# smart_auto_charger_2020-04-23_15-03-07.net
KiCad netlist of a schematic drawn in EasyEDA
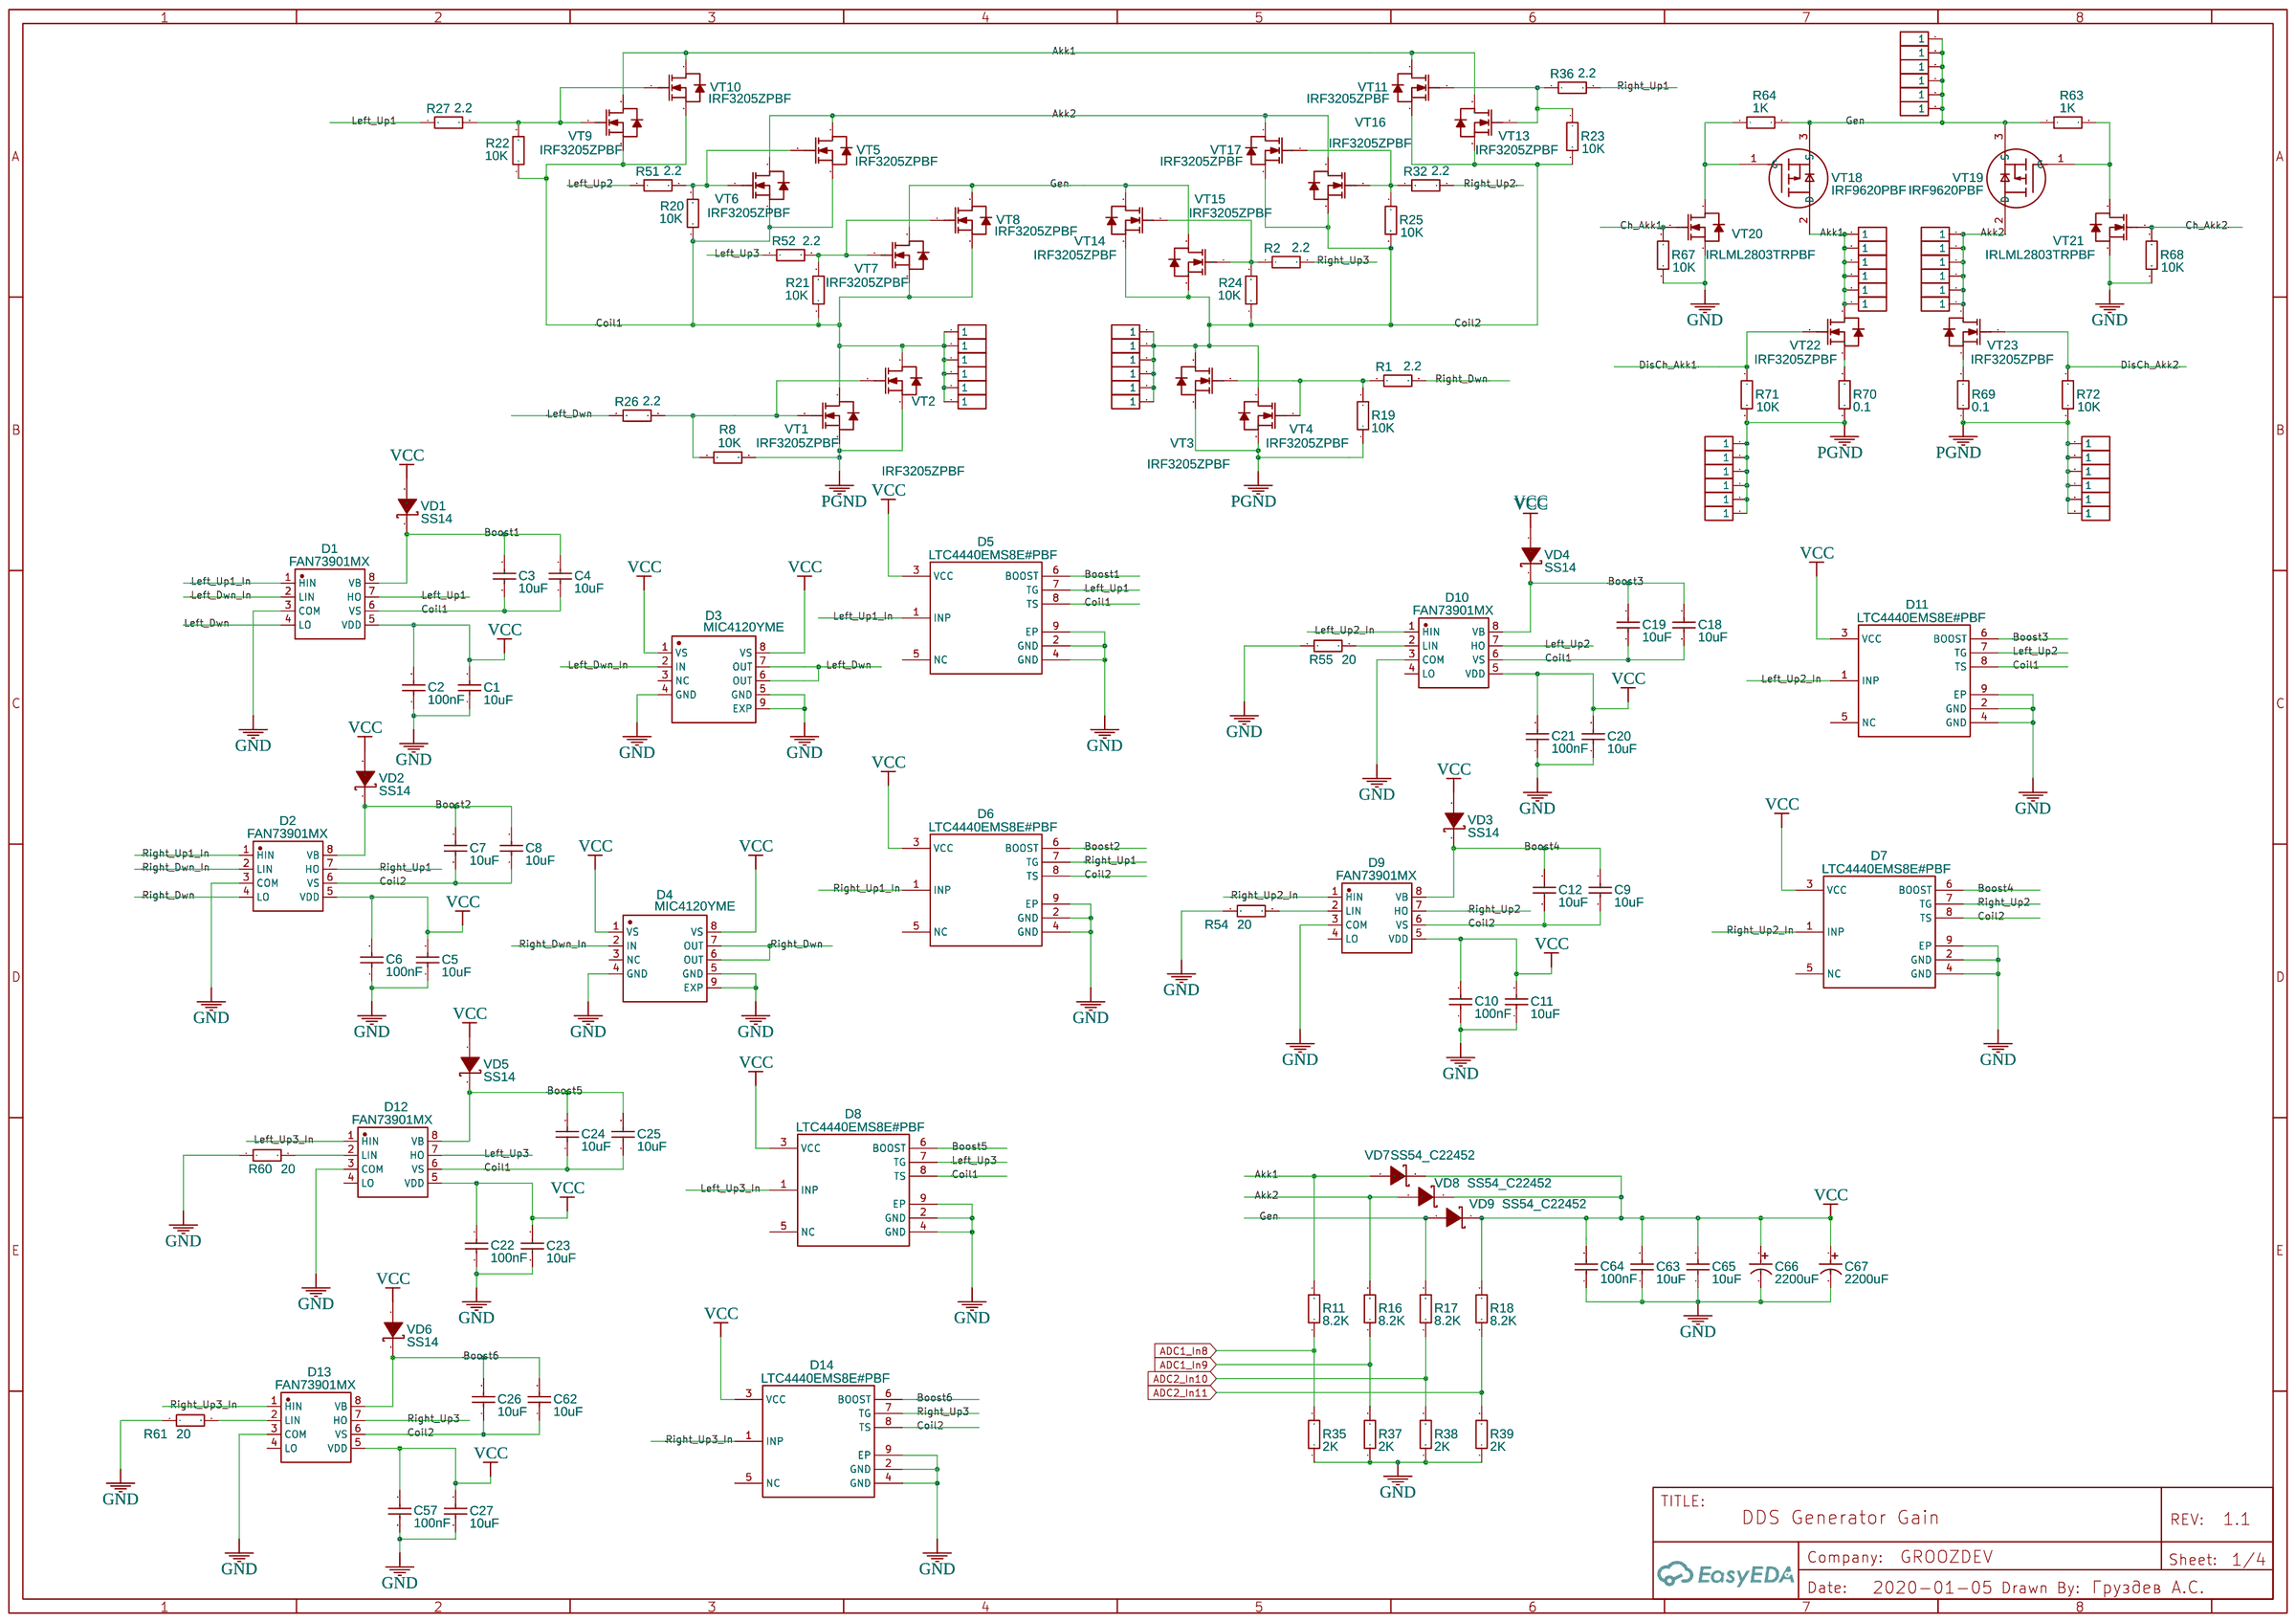
[diagram p0: First stage]
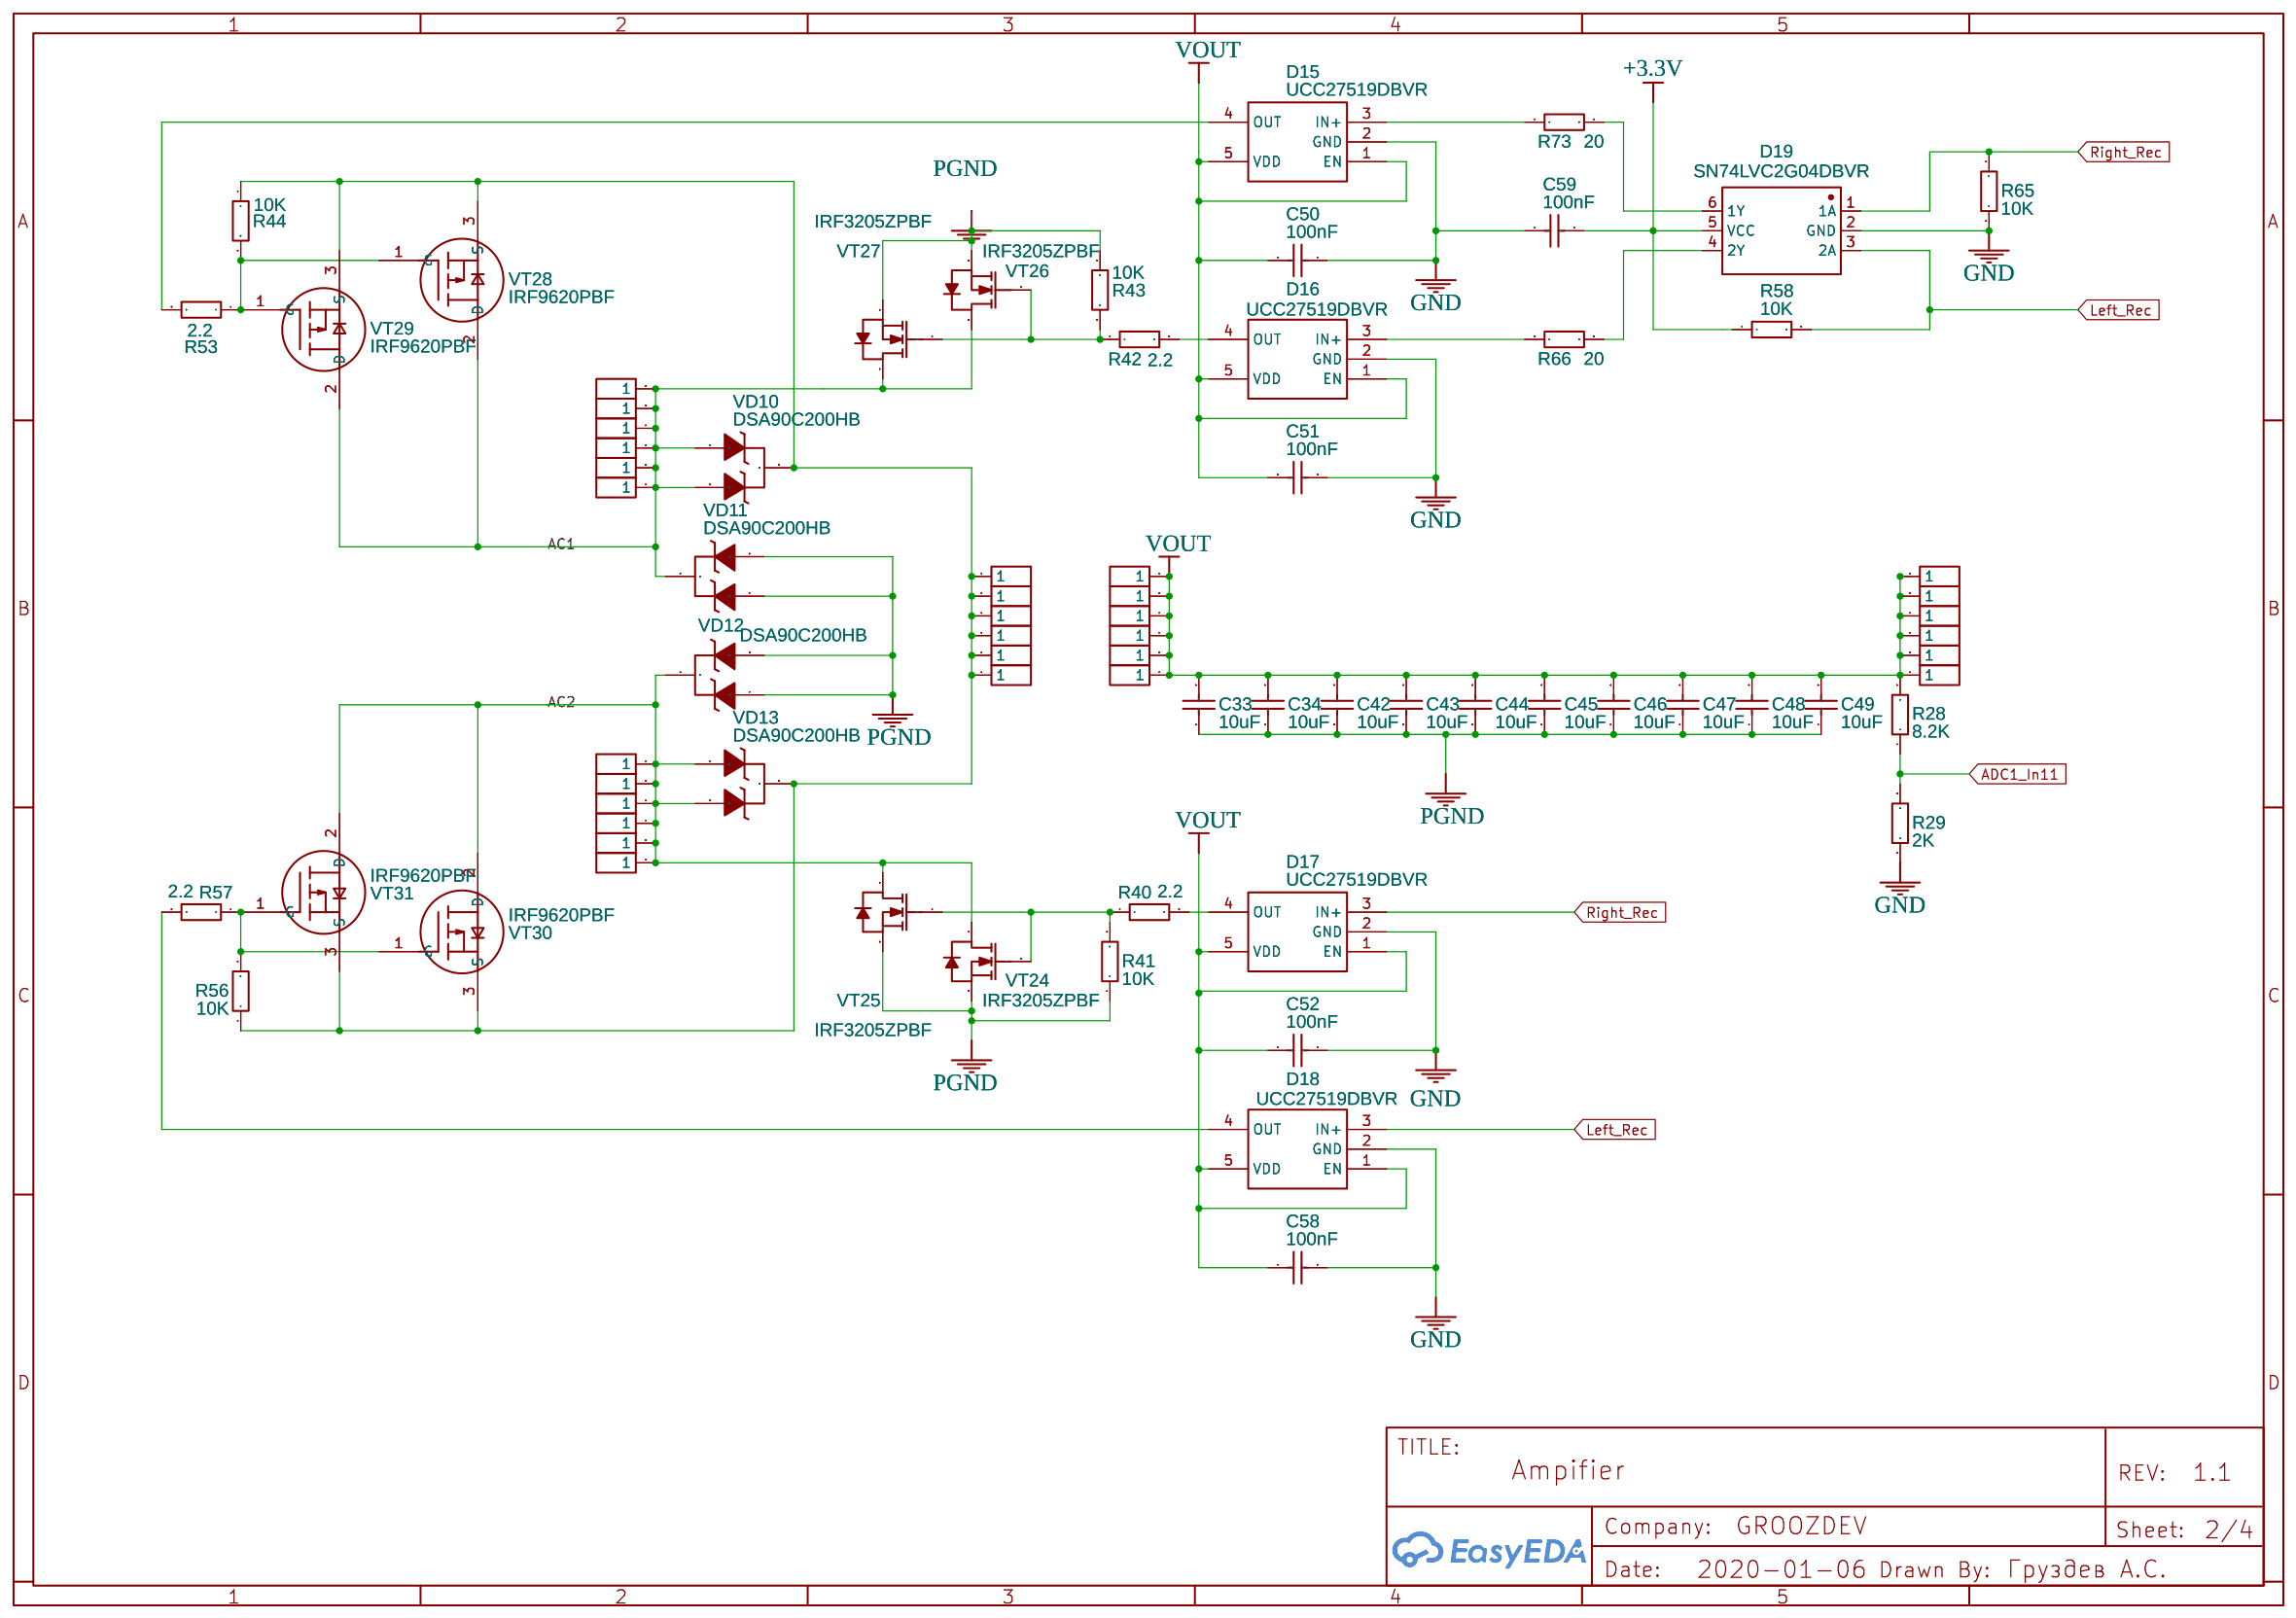
[diagram p1: Second stage]
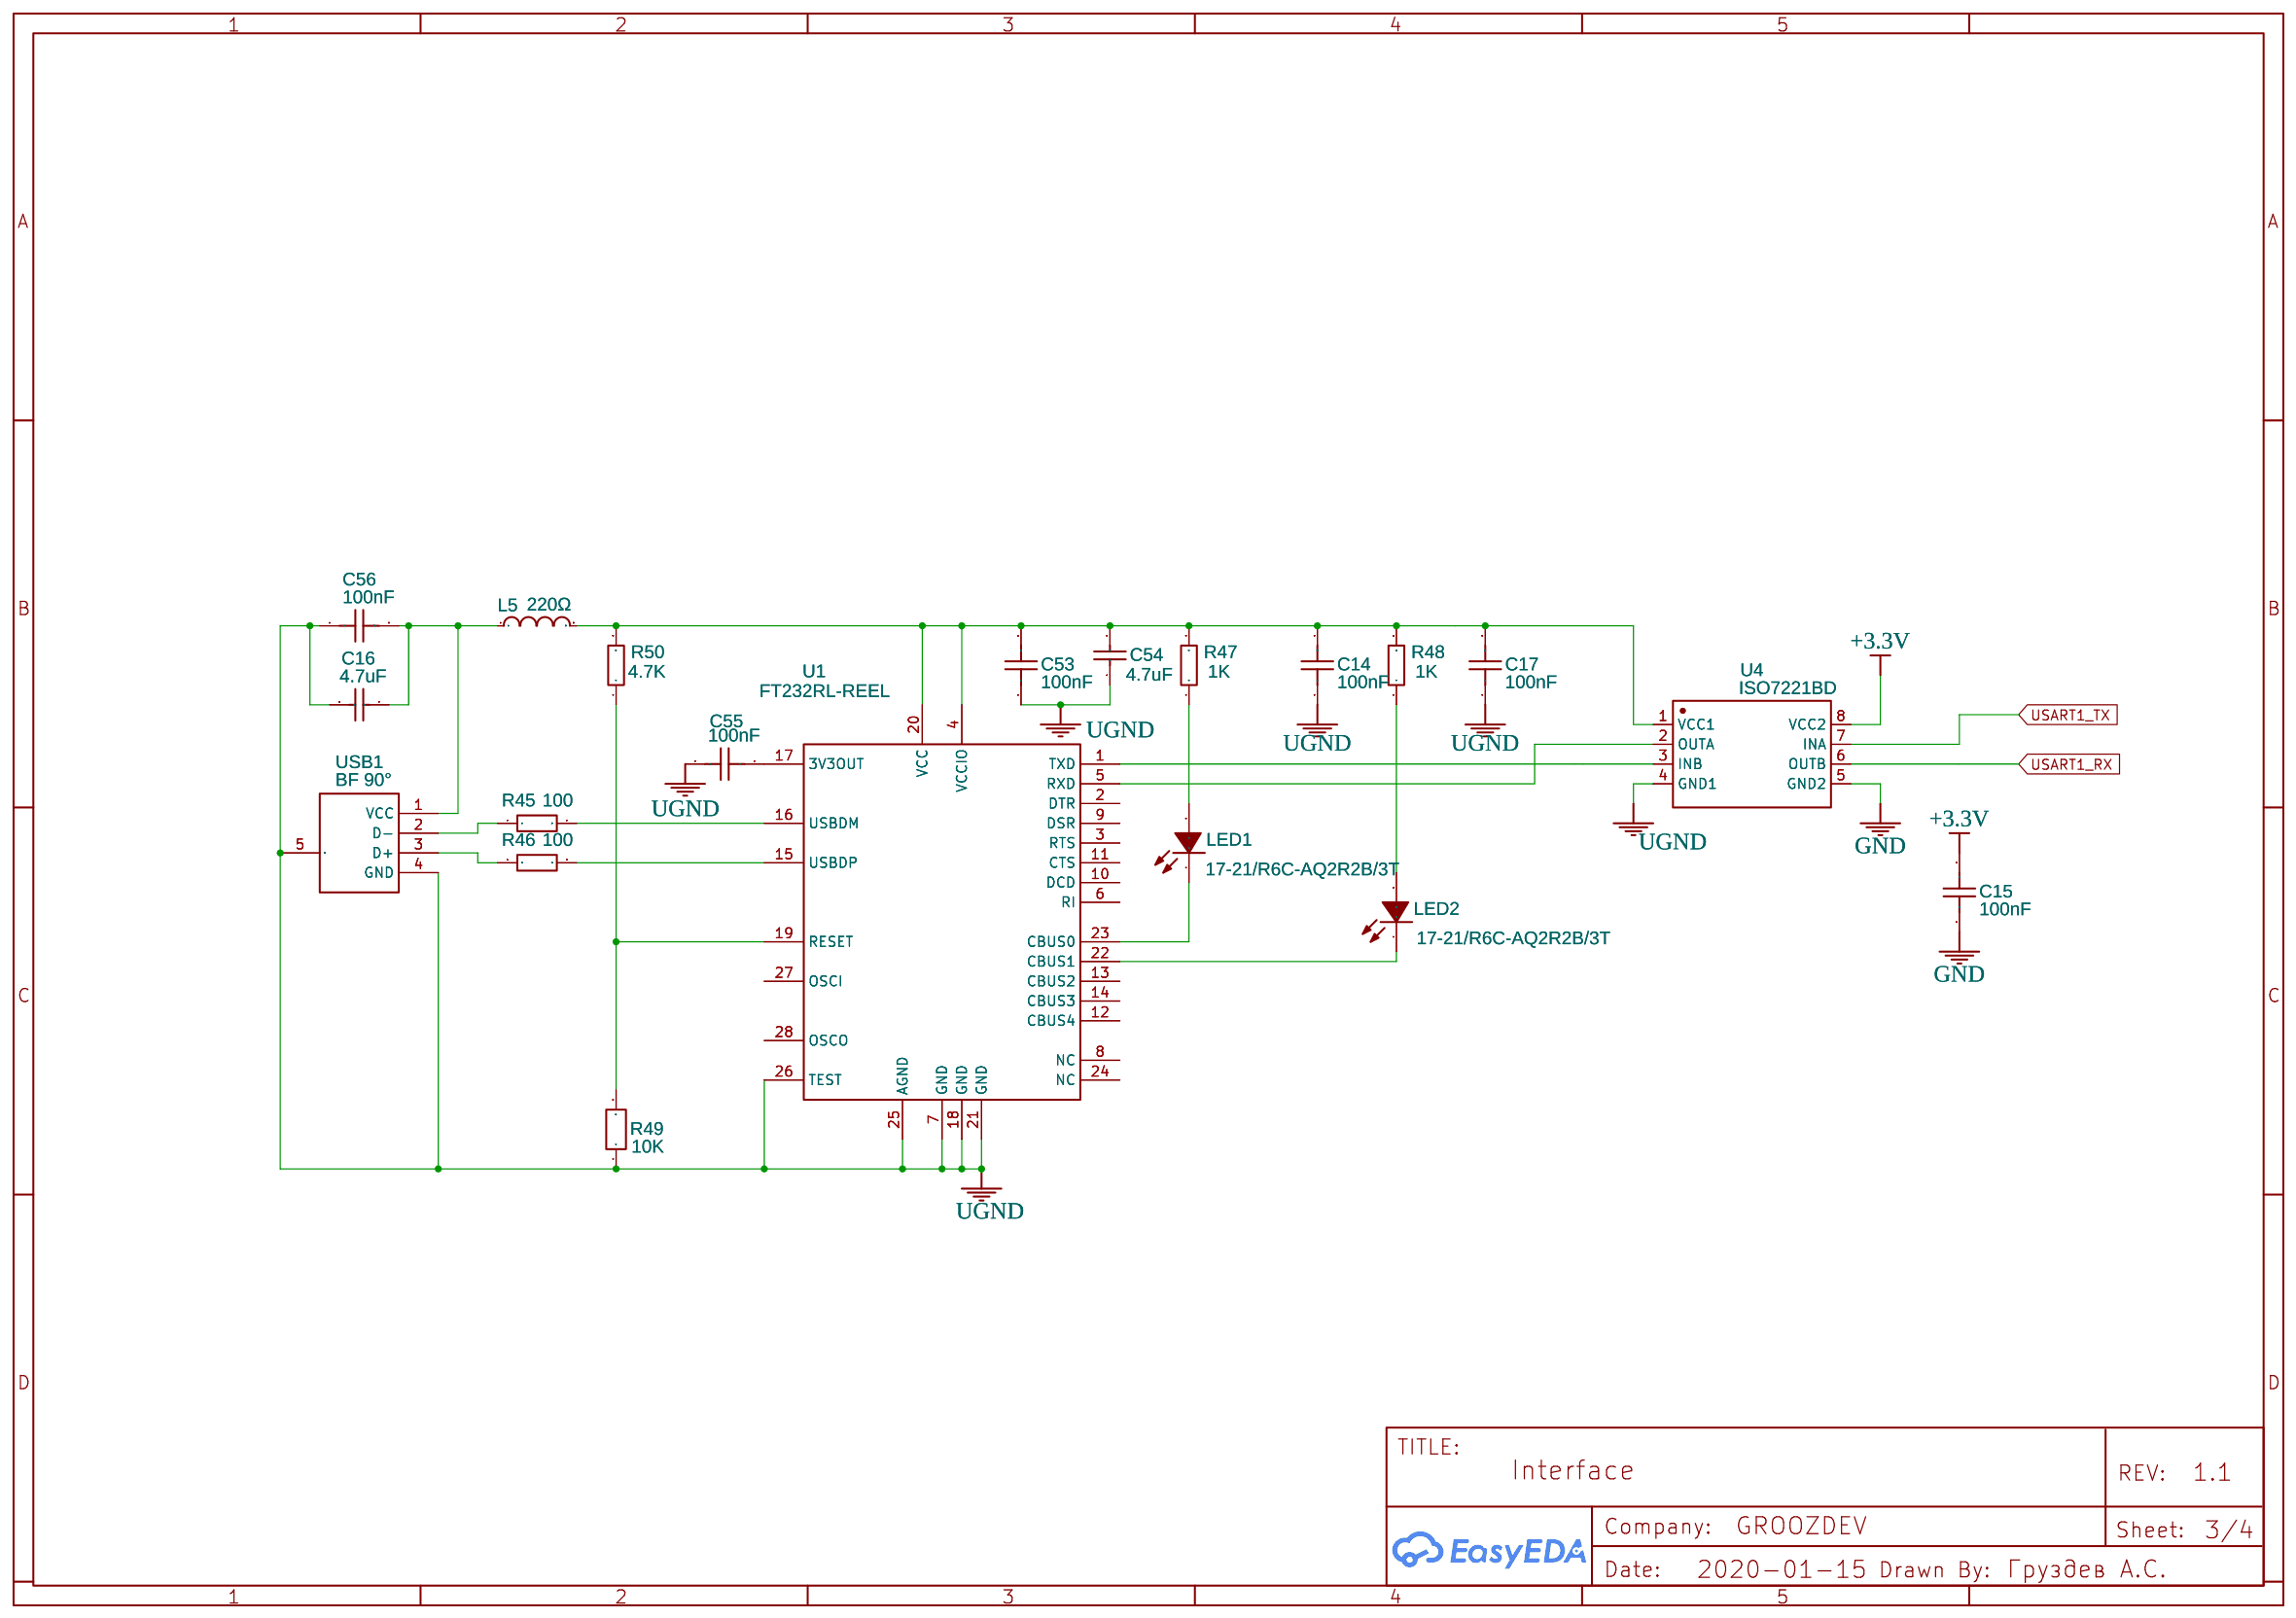
[diagram p2: USBtoVirtualCOM]
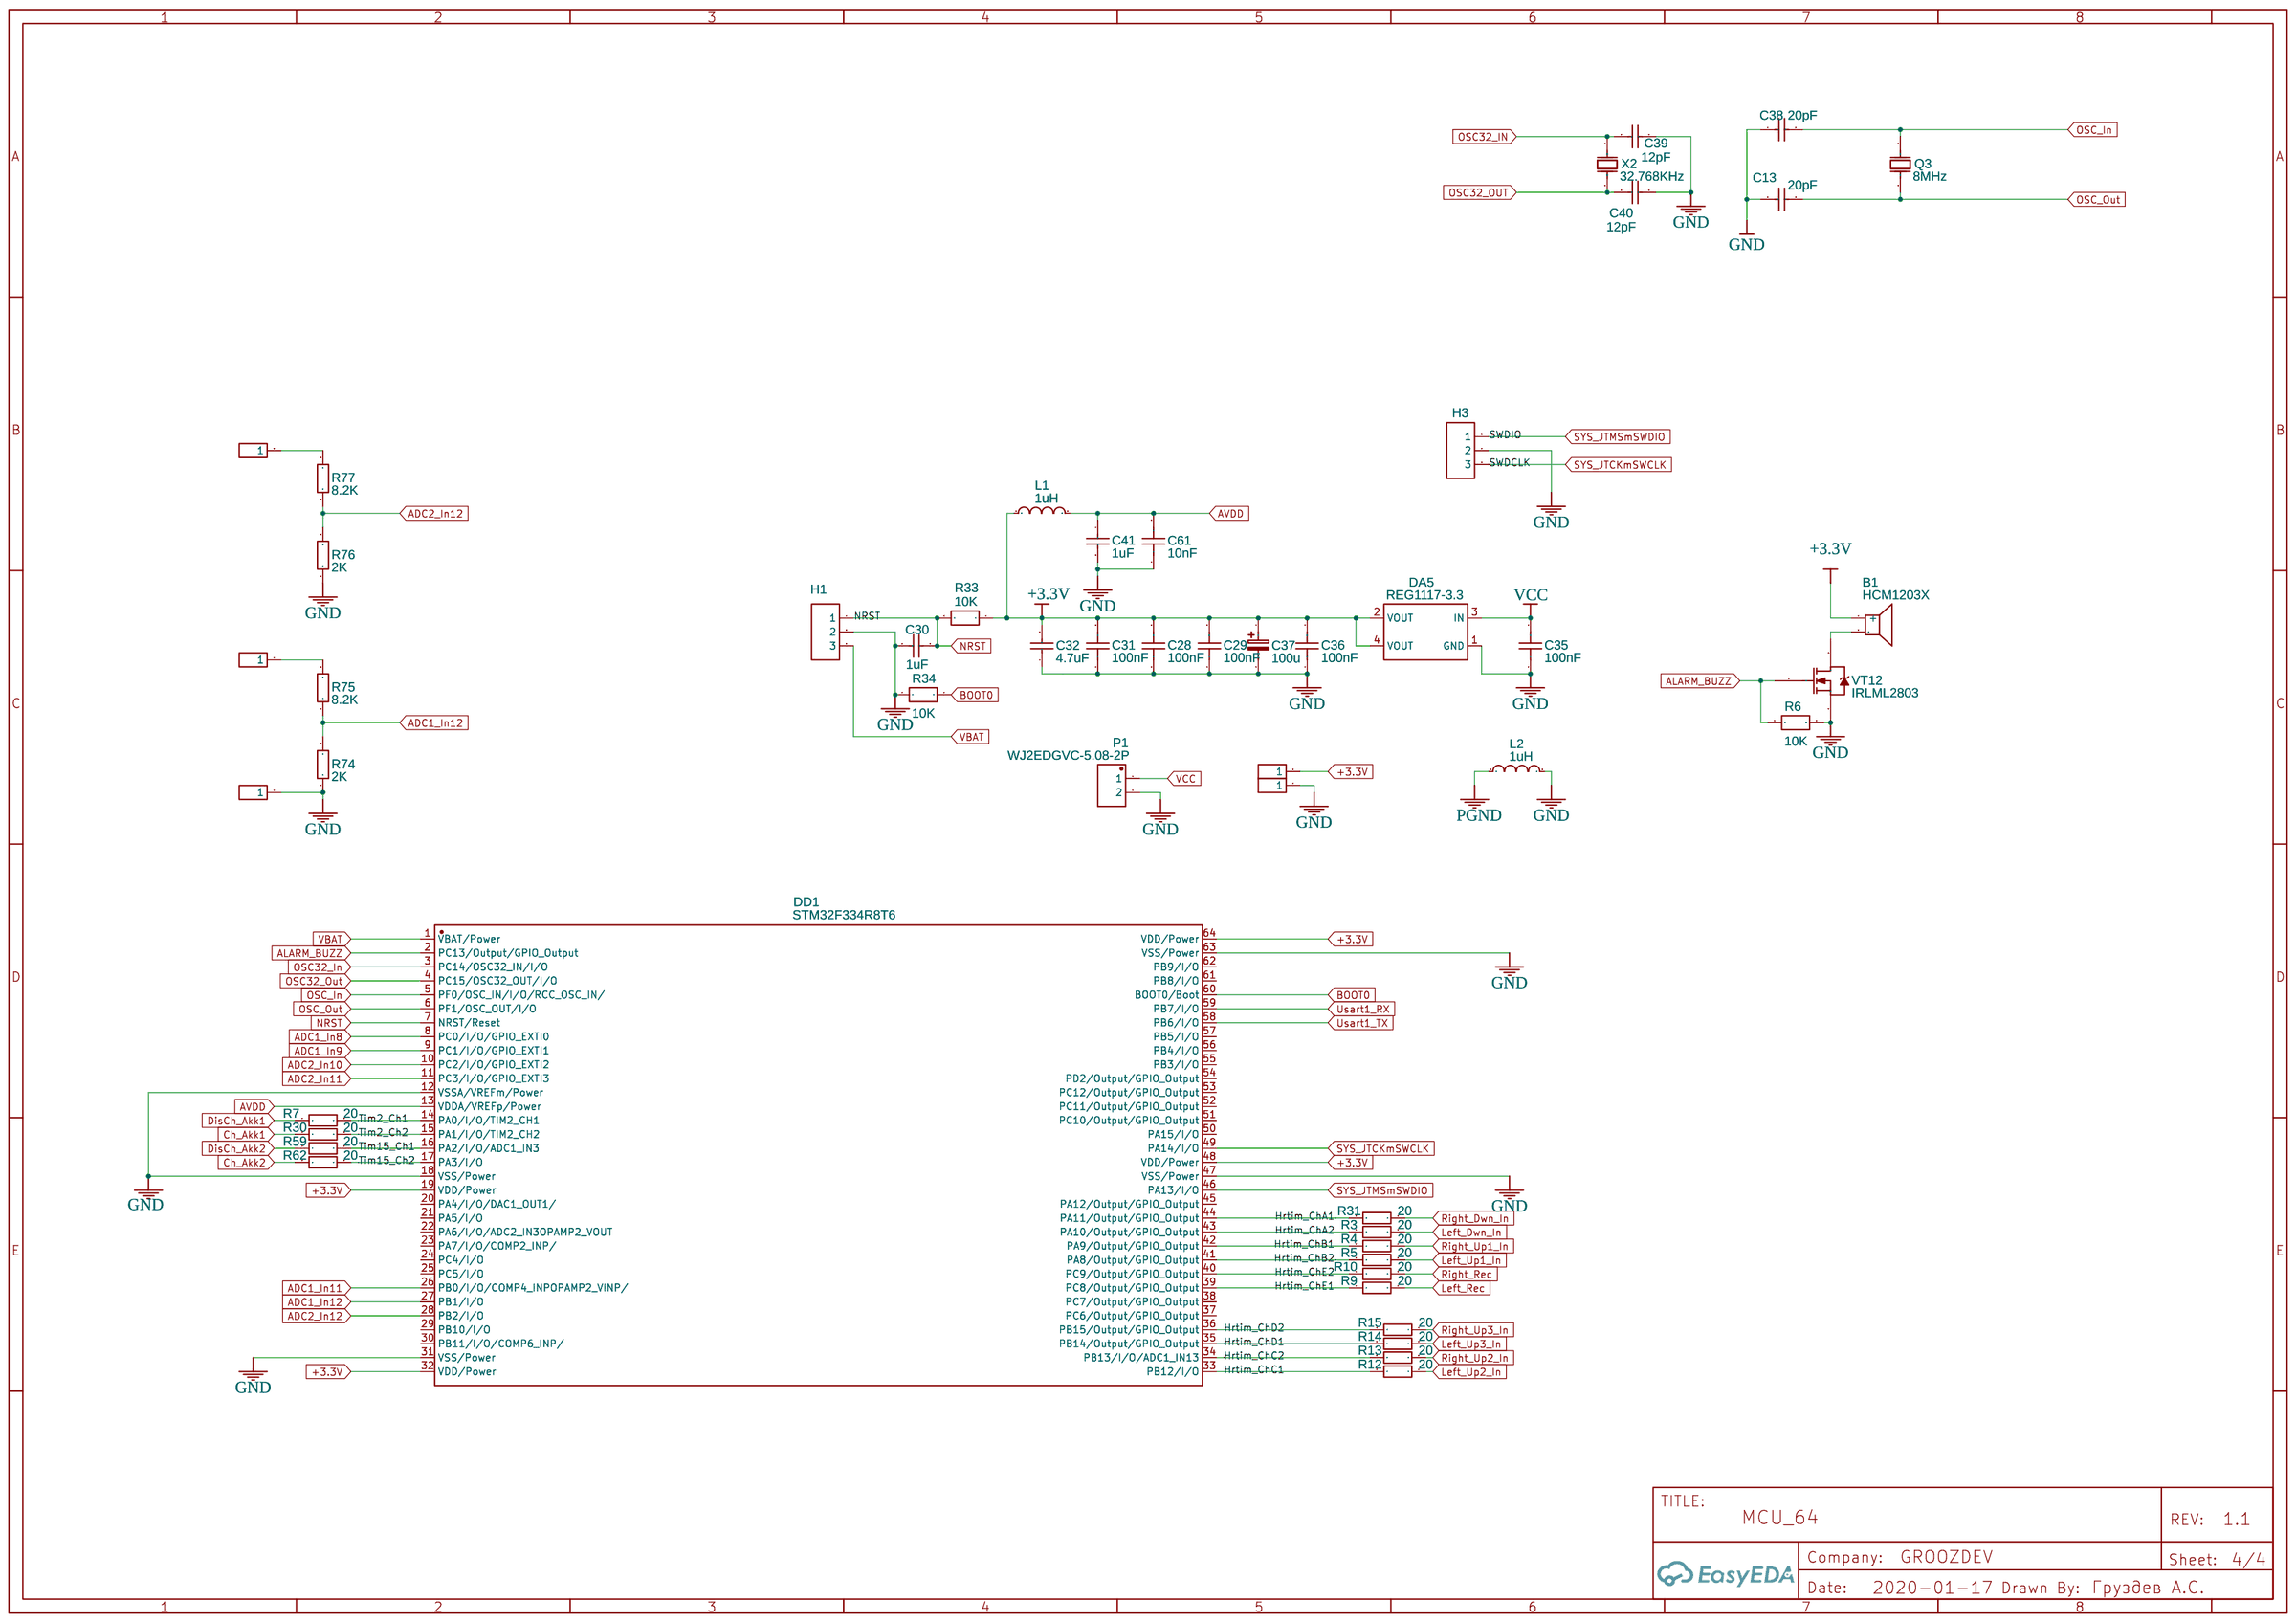
[diagram p3: MCU_64]

(export (version "E")
  (design (tool "Eeschema 10.0.6"))
  (components
    (comp (ref "C1")
      (value "10uF")
      (fields
        (field (name "BOM_Manufacturer Part") "CL31A106KBHNNNE")
        (field (name "BOM_Supplier Part") "C13585")
      )
      (libsource (lib "") (part "CL31A106KBHNNNE"))
    )
    (comp (ref "C2")
      (value "100nF")
      (fields
        (field (name "BOM_Manufacturer Part") "CL31B104KCFNNNE")
        (field (name "BOM_Supplier Part") "C1945")
      )
      (libsource (lib "") (part "CL31B104KCFNNNE"))
    )
    (comp (ref "C3")
      (value "10uF")
      (fields
        (field (name "BOM_Manufacturer Part") "CL31A106KBHNNNE")
        (field (name "BOM_Supplier Part") "C13585")
      )
      (libsource (lib "") (part "CL31A106KBHNNNE"))
    )
    (comp (ref "C4")
      (value "10uF")
      (fields
        (field (name "BOM_Manufacturer Part") "CL31A106KBHNNNE")
        (field (name "BOM_Supplier Part") "C13585")
      )
      (libsource (lib "") (part "CL31A106KBHNNNE"))
    )
    (comp (ref "C5")
      (value "10uF")
      (fields
        (field (name "BOM_Manufacturer Part") "CL31A106KBHNNNE")
        (field (name "BOM_Supplier Part") "C13585")
      )
      (libsource (lib "") (part "CL31A106KBHNNNE"))
    )
    (comp (ref "C6")
      (value "100nF")
      (fields
        (field (name "BOM_Manufacturer Part") "CL31B104KCFNNNE")
        (field (name "BOM_Supplier Part") "C1945")
      )
      (libsource (lib "") (part "CL31B104KCFNNNE"))
    )
    (comp (ref "C7")
      (value "10uF")
      (fields
        (field (name "BOM_Manufacturer Part") "CL31A106KBHNNNE")
        (field (name "BOM_Supplier Part") "C13585")
      )
      (libsource (lib "") (part "CL31A106KBHNNNE"))
    )
    (comp (ref "C8")
      (value "10uF")
      (fields
        (field (name "BOM_Manufacturer Part") "CL31A106KBHNNNE")
        (field (name "BOM_Supplier Part") "C13585")
      )
      (libsource (lib "") (part "CL31A106KBHNNNE"))
    )
    (comp (ref "C9")
      (value "10uF")
      (fields
        (field (name "BOM_Manufacturer Part") "CL31A106KBHNNNE")
        (field (name "BOM_Supplier Part") "C13585")
      )
      (libsource (lib "") (part "CL31A106KBHNNNE"))
    )
    (comp (ref "C10")
      (value "100nF")
      (fields
        (field (name "BOM_Manufacturer Part") "CL31B104KCFNNNE")
        (field (name "BOM_Supplier Part") "C1945")
      )
      (libsource (lib "") (part "CL31B104KCFNNNE"))
    )
    (comp (ref "C11")
      (value "10uF")
      (fields
        (field (name "BOM_Manufacturer Part") "CL31A106KBHNNNE")
        (field (name "BOM_Supplier Part") "C13585")
      )
      (libsource (lib "") (part "CL31A106KBHNNNE"))
    )
    (comp (ref "C12")
      (value "10uF")
      (fields
        (field (name "BOM_Manufacturer Part") "CL31A106KBHNNNE")
        (field (name "BOM_Supplier Part") "C13585")
      )
      (libsource (lib "") (part "CL31A106KBHNNNE"))
    )
    (comp (ref "C18")
      (value "10uF")
      (fields
        (field (name "BOM_Manufacturer Part") "CL31A106KBHNNNE")
        (field (name "BOM_Supplier Part") "C13585")
      )
      (libsource (lib "") (part "CL31A106KBHNNNE"))
    )
    (comp (ref "C19")
      (value "10uF")
      (fields
        (field (name "BOM_Manufacturer Part") "CL31A106KBHNNNE")
        (field (name "BOM_Supplier Part") "C13585")
      )
      (libsource (lib "") (part "CL31A106KBHNNNE"))
    )
    (comp (ref "C20")
      (value "10uF")
      (fields
        (field (name "BOM_Manufacturer Part") "CL31A106KBHNNNE")
        (field (name "BOM_Supplier Part") "C13585")
      )
      (libsource (lib "") (part "CL31A106KBHNNNE"))
    )
    (comp (ref "C21")
      (value "100nF")
      (fields
        (field (name "BOM_Manufacturer Part") "CL31B104KCFNNNE")
        (field (name "BOM_Supplier Part") "C1945")
      )
      (libsource (lib "") (part "CL31B104KCFNNNE"))
    )
    (comp (ref "C22")
      (value "100nF")
      (fields
        (field (name "BOM_Manufacturer Part") "CL31B104KCFNNNE")
        (field (name "BOM_Supplier Part") "C1945")
      )
      (libsource (lib "") (part "CL31B104KCFNNNE"))
    )
    (comp (ref "C23")
      (value "10uF")
      (fields
        (field (name "BOM_Manufacturer Part") "CL31A106KBHNNNE")
        (field (name "BOM_Supplier Part") "C13585")
      )
      (libsource (lib "") (part "CL31A106KBHNNNE"))
    )
    (comp (ref "C24")
      (value "10uF")
      (fields
        (field (name "BOM_Manufacturer Part") "CL31A106KBHNNNE")
        (field (name "BOM_Supplier Part") "C13585")
      )
      (libsource (lib "") (part "CL31A106KBHNNNE"))
    )
    (comp (ref "C25")
      (value "10uF")
      (fields
        (field (name "BOM_Manufacturer Part") "CL31A106KBHNNNE")
        (field (name "BOM_Supplier Part") "C13585")
      )
      (libsource (lib "") (part "CL31A106KBHNNNE"))
    )
    (comp (ref "C26")
      (value "10uF")
      (fields
        (field (name "BOM_Manufacturer Part") "CL31A106KBHNNNE")
        (field (name "BOM_Supplier Part") "C13585")
      )
      (libsource (lib "") (part "CL31A106KBHNNNE"))
    )
    (comp (ref "C27")
      (value "10uF")
      (fields
        (field (name "BOM_Manufacturer Part") "CL31A106KBHNNNE")
        (field (name "BOM_Supplier Part") "C13585")
      )
      (libsource (lib "") (part "CL31A106KBHNNNE"))
    )
    (comp (ref "C57")
      (value "100nF")
      (fields
        (field (name "BOM_Manufacturer Part") "CL31B104KCFNNNE")
        (field (name "BOM_Supplier Part") "C1945")
      )
      (libsource (lib "") (part "CL31B104KCFNNNE"))
    )
    (comp (ref "C62")
      (value "10uF")
      (fields
        (field (name "BOM_Manufacturer Part") "CL31A106KBHNNNE")
        (field (name "BOM_Supplier Part") "C13585")
      )
      (libsource (lib "") (part "CL31A106KBHNNNE"))
    )
    (comp (ref "C63")
      (value "10uF")
      (fields
        (field (name "BOM_Manufacturer Part") "CL31A106KBHNNNE")
        (field (name "BOM_Supplier Part") "C13585")
      )
      (libsource (lib "") (part "CL31A106KBHNNNE"))
    )
    (comp (ref "C64")
      (value "100nF")
      (fields
        (field (name "BOM_Manufacturer Part") "CL31B104KCFNNNE")
        (field (name "BOM_Supplier Part") "C1945")
      )
      (libsource (lib "") (part "CL31B104KCFNNNE"))
    )
    (comp (ref "C65")
      (value "10uF")
      (fields
        (field (name "BOM_Manufacturer Part") "CL31A106KBHNNNE")
        (field (name "BOM_Supplier Part") "C13585")
      )
      (libsource (lib "") (part "CL31A106KBHNNNE"))
    )
    (comp (ref "C66")
      (value "2200uF")
      (fields
        (field (name "BOM_Manufacturer Part") "2200uF 35V 16X25")
        (field (name "BOM_Supplier Part") "C2763")
      )
      (libsource (lib "") (part "2200uF 35V 16X25"))
    )
    (comp (ref "C67")
      (value "2200uF")
      (fields
        (field (name "BOM_Manufacturer Part") "2200uF 35V 16X25")
        (field (name "BOM_Supplier Part") "C2763")
      )
      (libsource (lib "") (part "2200uF 35V 16X25"))
    )
    (comp (ref "D1")
      (value "FAN73901MX")
      (fields (field (name "BOM_Supplier Part") "C380794"))
      (libsource (lib "") (part "FAN73901MX"))
    )
    (comp (ref "D2")
      (value "FAN73901MX")
      (fields (field (name "BOM_Supplier Part") "C380794"))
      (libsource (lib "") (part "FAN73901MX"))
    )
    (comp (ref "D3")
      (value "MIC4120YME")
      (fields (field (name "BOM_Supplier Part") "C145580"))
      (libsource (lib "") (part "MIC4120YME"))
    )
    (comp (ref "D4")
      (value "MIC4120YME")
      (fields (field (name "BOM_Supplier Part") "C145580"))
      (libsource (lib "") (part "MIC4120YME"))
    )
    (comp (ref "D5")
      (value "LTC4440EMS8E#PBF")
      (fields (field (name "BOM_Supplier Part") "C107973"))
      (libsource (lib "") (part "LTC4440EMS8E#PBF"))
    )
    (comp (ref "D6")
      (value "LTC4440EMS8E#PBF")
      (fields (field (name "BOM_Supplier Part") "C107973"))
      (libsource (lib "") (part "LTC4440EMS8E#PBF"))
    )
    (comp (ref "D7")
      (value "LTC4440EMS8E#PBF")
      (fields (field (name "BOM_Supplier Part") "C107973"))
      (libsource (lib "") (part "LTC4440EMS8E#PBF"))
    )
    (comp (ref "D8")
      (value "LTC4440EMS8E#PBF")
      (fields (field (name "BOM_Supplier Part") "C107973"))
      (libsource (lib "") (part "LTC4440EMS8E#PBF"))
    )
    (comp (ref "D9")
      (value "FAN73901MX")
      (fields (field (name "BOM_Supplier Part") "C380794"))
      (libsource (lib "") (part "FAN73901MX"))
    )
    (comp (ref "D10")
      (value "FAN73901MX")
      (fields (field (name "BOM_Supplier Part") "C380794"))
      (libsource (lib "") (part "FAN73901MX"))
    )
    (comp (ref "D11")
      (value "LTC4440EMS8E#PBF")
      (fields (field (name "BOM_Supplier Part") "C107973"))
      (libsource (lib "") (part "LTC4440EMS8E#PBF"))
    )
    (comp (ref "D12")
      (value "FAN73901MX")
      (fields (field (name "BOM_Supplier Part") "C380794"))
      (libsource (lib "") (part "FAN73901MX"))
    )
    (comp (ref "D13")
      (value "FAN73901MX")
      (fields (field (name "BOM_Supplier Part") "C380794"))
      (libsource (lib "") (part "FAN73901MX"))
    )
    (comp (ref "D14")
      (value "LTC4440EMS8E#PBF")
      (fields (field (name "BOM_Supplier Part") "C107973"))
      (libsource (lib "") (part "LTC4440EMS8E#PBF"))
    )
    (comp (ref "P4")
      (value "Header-Male-2.54_1x1")
      (fields (field (name "BOM_Supplier Part") "C81276"))
      (libsource (lib "") (part "Header-Male-2.54_1x1_1"))
    )
    (comp (ref "P5")
      (value "Header-Male-2.54_1x1")
      (fields (field (name "BOM_Supplier Part") "C81276"))
      (libsource (lib "") (part "Header-Male-2.54_1x1_1"))
    )
    (comp (ref "P6")
      (value "Header-Male-2.54_1x1")
      (fields (field (name "BOM_Supplier Part") "C81276"))
      (libsource (lib "") (part "Header-Male-2.54_1x1_1"))
    )
    (comp (ref "P7")
      (value "Header-Male-2.54_1x1")
      (fields (field (name "BOM_Supplier Part") "C81276"))
      (libsource (lib "") (part "Header-Male-2.54_1x1"))
    )
    (comp (ref "P8")
      (value "Header-Male-2.54_1x1")
      (fields (field (name "BOM_Supplier Part") "C81276"))
      (libsource (lib "") (part "Header-Male-2.54_1x1"))
    )
    (comp (ref "P9")
      (value "Header-Male-2.54_1x1")
      (fields (field (name "BOM_Supplier Part") "C81276"))
      (libsource (lib "") (part "Header-Male-2.54_1x1"))
    )
    (comp (ref "P10")
      (value "Header-Male-2.54_1x1")
      (fields (field (name "BOM_Supplier Part") "C81276"))
      (libsource (lib "") (part "Header-Male-2.54_1x1_1"))
    )
    (comp (ref "P11")
      (value "Header-Male-2.54_1x1")
      (fields (field (name "BOM_Supplier Part") "C81276"))
      (libsource (lib "") (part "Header-Male-2.54_1x1_1"))
    )
    (comp (ref "P12")
      (value "Header-Male-2.54_1x1")
      (fields (field (name "BOM_Supplier Part") "C81276"))
      (libsource (lib "") (part "Header-Male-2.54_1x1_1"))
    )
    (comp (ref "P13")
      (value "Header-Male-2.54_1x1")
      (fields (field (name "BOM_Supplier Part") "C81276"))
      (libsource (lib "") (part "Header-Male-2.54_1x1"))
    )
    (comp (ref "P14")
      (value "Header-Male-2.54_1x1")
      (fields (field (name "BOM_Supplier Part") "C81276"))
      (libsource (lib "") (part "Header-Male-2.54_1x1"))
    )
    (comp (ref "P15")
      (value "Header-Male-2.54_1x1")
      (fields (field (name "BOM_Supplier Part") "C81276"))
      (libsource (lib "") (part "Header-Male-2.54_1x1"))
    )
    (comp (ref "P16")
      (value "Header-Male-2.54_1x1")
      (fields (field (name "BOM_Supplier Part") "C81276"))
      (libsource (lib "") (part "Header-Male-2.54_1x1"))
    )
    (comp (ref "P17")
      (value "Header-Male-2.54_1x1")
      (fields (field (name "BOM_Supplier Part") "C81276"))
      (libsource (lib "") (part "Header-Male-2.54_1x1"))
    )
    (comp (ref "P32")
      (value "Header-Male-2.54_1x1")
      (fields (field (name "BOM_Supplier Part") "C81276"))
      (libsource (lib "") (part "Header-Male-2.54_1x1"))
    )
    (comp (ref "P33")
      (value "Header-Male-2.54_1x1")
      (fields (field (name "BOM_Supplier Part") "C81276"))
      (libsource (lib "") (part "Header-Male-2.54_1x1_1"))
    )
    (comp (ref "P34")
      (value "Header-Male-2.54_1x1")
      (fields (field (name "BOM_Supplier Part") "C81276"))
      (libsource (lib "") (part "Header-Male-2.54_1x1_1"))
    )
    (comp (ref "P35")
      (value "Header-Male-2.54_1x1")
      (fields (field (name "BOM_Supplier Part") "C81276"))
      (libsource (lib "") (part "Header-Male-2.54_1x1_1"))
    )
    (comp (ref "P36")
      (value "Header-Male-2.54_1x1")
      (fields (field (name "BOM_Supplier Part") "C81276"))
      (libsource (lib "") (part "Header-Male-2.54_1x1_1"))
    )
    (comp (ref "P37")
      (value "Header-Male-2.54_1x1")
      (fields (field (name "BOM_Supplier Part") "C81276"))
      (libsource (lib "") (part "Header-Male-2.54_1x1"))
    )
    (comp (ref "P38")
      (value "Header-Male-2.54_1x1")
      (fields (field (name "BOM_Supplier Part") "C81276"))
      (libsource (lib "") (part "Header-Male-2.54_1x1"))
    )
    (comp (ref "P39")
      (value "Header-Male-2.54_1x1")
      (fields (field (name "BOM_Supplier Part") "C81276"))
      (libsource (lib "") (part "Header-Male-2.54_1x1"))
    )
    (comp (ref "P40")
      (value "Header-Male-2.54_1x1")
      (fields (field (name "BOM_Supplier Part") "C81276"))
      (libsource (lib "") (part "Header-Male-2.54_1x1_1"))
    )
    (comp (ref "P41")
      (value "Header-Male-2.54_1x1")
      (fields (field (name "BOM_Supplier Part") "C81276"))
      (libsource (lib "") (part "Header-Male-2.54_1x1_1"))
    )
    (comp (ref "P42")
      (value "Header-Male-2.54_1x1")
      (fields (field (name "BOM_Supplier Part") "C81276"))
      (libsource (lib "") (part "Header-Male-2.54_1x1"))
    )
    (comp (ref "P43")
      (value "Header-Male-2.54_1x1")
      (fields (field (name "BOM_Supplier Part") "C81276"))
      (libsource (lib "") (part "Header-Male-2.54_1x1"))
    )
    (comp (ref "P44")
      (value "Header-Male-2.54_1x1")
      (fields (field (name "BOM_Supplier Part") "C81276"))
      (libsource (lib "") (part "Header-Male-2.54_1x1"))
    )
    (comp (ref "P45")
      (value "Header-Male-2.54_1x1")
      (fields (field (name "BOM_Supplier Part") "C81276"))
      (libsource (lib "") (part "Header-Male-2.54_1x1"))
    )
    (comp (ref "P46")
      (value "Header-Male-2.54_1x1")
      (fields (field (name "BOM_Supplier Part") "C81276"))
      (libsource (lib "") (part "Header-Male-2.54_1x1"))
    )
    (comp (ref "P47")
      (value "Header-Male-2.54_1x1")
      (fields (field (name "BOM_Supplier Part") "C81276"))
      (libsource (lib "") (part "Header-Male-2.54_1x1"))
    )
    (comp (ref "P48")
      (value "Header-Male-2.54_1x1")
      (fields (field (name "BOM_Supplier Part") "C81276"))
      (libsource (lib "") (part "Header-Male-2.54_1x1"))
    )
    (comp (ref "P49")
      (value "Header-Male-2.54_1x1")
      (fields (field (name "BOM_Supplier Part") "C81276"))
      (libsource (lib "") (part "Header-Male-2.54_1x1"))
    )
    (comp (ref "P50")
      (value "Header-Male-2.54_1x1")
      (fields (field (name "BOM_Supplier Part") "C81276"))
      (libsource (lib "") (part "Header-Male-2.54_1x1"))
    )
    (comp (ref "P51")
      (value "Header-Male-2.54_1x1")
      (fields (field (name "BOM_Supplier Part") "C81276"))
      (libsource (lib "") (part "Header-Male-2.54_1x1"))
    )
    (comp (ref "P52")
      (value "Header-Male-2.54_1x1")
      (fields (field (name "BOM_Supplier Part") "C81276"))
      (libsource (lib "") (part "Header-Male-2.54_1x1"))
    )
    (comp (ref "P53")
      (value "Header-Male-2.54_1x1")
      (fields (field (name "BOM_Supplier Part") "C81276"))
      (libsource (lib "") (part "Header-Male-2.54_1x1"))
    )
    (comp (ref "P54")
      (value "Header-Male-2.54_1x1")
      (fields (field (name "BOM_Supplier Part") "C81276"))
      (libsource (lib "") (part "Header-Male-2.54_1x1_1"))
    )
    (comp (ref "P55")
      (value "Header-Male-2.54_1x1")
      (fields (field (name "BOM_Supplier Part") "C81276"))
      (libsource (lib "") (part "Header-Male-2.54_1x1_1"))
    )
    (comp (ref "P56")
      (value "Header-Male-2.54_1x1")
      (fields (field (name "BOM_Supplier Part") "C81276"))
      (libsource (lib "") (part "Header-Male-2.54_1x1_1"))
    )
    (comp (ref "P57")
      (value "Header-Male-2.54_1x1")
      (fields (field (name "BOM_Supplier Part") "C81276"))
      (libsource (lib "") (part "Header-Male-2.54_1x1_1"))
    )
    (comp (ref "P58")
      (value "Header-Male-2.54_1x1")
      (fields (field (name "BOM_Supplier Part") "C81276"))
      (libsource (lib "") (part "Header-Male-2.54_1x1_1"))
    )
    (comp (ref "P59")
      (value "Header-Male-2.54_1x1")
      (fields (field (name "BOM_Supplier Part") "C81276"))
      (libsource (lib "") (part "Header-Male-2.54_1x1_1"))
    )
    (comp (ref "R1")
      (value "2.2")
      (fields
        (field (name "BOM_Manufacturer Part") "0603WAF220KT5E")
        (field (name "BOM_Supplier Part") "C22939")
      )
      (libsource (lib "") (part "0603WAF220KT5E"))
    )
    (comp (ref "R2")
      (value "2.2")
      (fields
        (field (name "BOM_Manufacturer Part") "0603WAF220KT5E")
        (field (name "BOM_Supplier Part") "C22939")
      )
      (libsource (lib "") (part "0603WAF220KT5E"))
    )
    (comp (ref "R8")
      (value "10K")
      (fields
        (field (name "BOM_Manufacturer Part") "0805W8F1002T5E")
        (field (name "BOM_Supplier Part") "C17414")
      )
      (libsource (lib "") (part "0805W8F1002T5E_2"))
    )
    (comp (ref "R11")
      (value "8.2K")
      (fields
        (field (name "BOM_Manufacturer Part") "0805W8F8201T5E")
        (field (name "BOM_Supplier Part") "C17828")
      )
      (libsource (lib "") (part "0805W8F8201T5E"))
    )
    (comp (ref "R16")
      (value "8.2K")
      (fields
        (field (name "BOM_Manufacturer Part") "0805W8F8201T5E")
        (field (name "BOM_Supplier Part") "C17828")
      )
      (libsource (lib "") (part "0805W8F8201T5E"))
    )
    (comp (ref "R17")
      (value "8.2K")
      (fields
        (field (name "BOM_Manufacturer Part") "0805W8F8201T5E")
        (field (name "BOM_Supplier Part") "C17828")
      )
      (libsource (lib "") (part "0805W8F8201T5E"))
    )
    (comp (ref "R18")
      (value "8.2K")
      (fields
        (field (name "BOM_Manufacturer Part") "0805W8F8201T5E")
        (field (name "BOM_Supplier Part") "C17828")
      )
      (libsource (lib "") (part "0805W8F8201T5E"))
    )
    (comp (ref "R19")
      (value "10K")
      (fields
        (field (name "BOM_Manufacturer Part") "0805W8F1002T5E")
        (field (name "BOM_Supplier Part") "C17414")
      )
      (libsource (lib "") (part "0805W8F1002T5E"))
    )
    (comp (ref "R20")
      (value "10K")
      (fields
        (field (name "BOM_Manufacturer Part") "0805W8F1002T5E")
        (field (name "BOM_Supplier Part") "C17414")
      )
      (libsource (lib "") (part "0805W8F1002T5E"))
    )
    (comp (ref "R21")
      (value "10K")
      (fields
        (field (name "BOM_Manufacturer Part") "0805W8F1002T5E")
        (field (name "BOM_Supplier Part") "C17414")
      )
      (libsource (lib "") (part "0805W8F1002T5E"))
    )
    (comp (ref "R22")
      (value "10K")
      (fields
        (field (name "BOM_Manufacturer Part") "0805W8F1002T5E")
        (field (name "BOM_Supplier Part") "C17414")
      )
      (libsource (lib "") (part "0805W8F1002T5E"))
    )
    (comp (ref "R23")
      (value "10K")
      (fields
        (field (name "BOM_Manufacturer Part") "0805W8F1002T5E")
        (field (name "BOM_Supplier Part") "C17414")
      )
      (libsource (lib "") (part "0805W8F1002T5E_1"))
    )
    (comp (ref "R24")
      (value "10K")
      (fields
        (field (name "BOM_Manufacturer Part") "0805W8F1002T5E")
        (field (name "BOM_Supplier Part") "C17414")
      )
      (libsource (lib "") (part "0805W8F1002T5E"))
    )
    (comp (ref "R25")
      (value "10K")
      (fields
        (field (name "BOM_Manufacturer Part") "0805W8F1002T5E")
        (field (name "BOM_Supplier Part") "C17414")
      )
      (libsource (lib "") (part "0805W8F1002T5E_1"))
    )
    (comp (ref "R26")
      (value "2.2")
      (fields
        (field (name "BOM_Manufacturer Part") "0603WAF220KT5E")
        (field (name "BOM_Supplier Part") "C22939")
      )
      (libsource (lib "") (part "0603WAF220KT5E"))
    )
    (comp (ref "R27")
      (value "2.2")
      (fields
        (field (name "BOM_Manufacturer Part") "0603WAF220KT5E")
        (field (name "BOM_Supplier Part") "C22939")
      )
      (libsource (lib "") (part "0603WAF220KT5E"))
    )
    (comp (ref "R32")
      (value "2.2")
      (fields
        (field (name "BOM_Manufacturer Part") "0603WAF220KT5E")
        (field (name "BOM_Supplier Part") "C22939")
      )
      (libsource (lib "") (part "0603WAF220KT5E"))
    )
    (comp (ref "R35")
      (value "2K")
      (fields
        (field (name "BOM_Manufacturer Part") "0805W8F2001T5E")
        (field (name "BOM_Supplier Part") "C17604")
      )
      (libsource (lib "") (part "0805W8F2001T5E"))
    )
    (comp (ref "R36")
      (value "2.2")
      (fields
        (field (name "BOM_Manufacturer Part") "0603WAF220KT5E")
        (field (name "BOM_Supplier Part") "C22939")
      )
      (libsource (lib "") (part "0603WAF220KT5E"))
    )
    (comp (ref "R37")
      (value "2K")
      (fields
        (field (name "BOM_Manufacturer Part") "0805W8F2001T5E")
        (field (name "BOM_Supplier Part") "C17604")
      )
      (libsource (lib "") (part "0805W8F2001T5E"))
    )
    (comp (ref "R38")
      (value "2K")
      (fields
        (field (name "BOM_Manufacturer Part") "0805W8F2001T5E")
        (field (name "BOM_Supplier Part") "C17604")
      )
      (libsource (lib "") (part "0805W8F2001T5E"))
    )
    (comp (ref "R39")
      (value "2K")
      (fields
        (field (name "BOM_Manufacturer Part") "0805W8F2001T5E")
        (field (name "BOM_Supplier Part") "C17604")
      )
      (libsource (lib "") (part "0805W8F2001T5E"))
    )
    (comp (ref "R51")
      (value "2.2")
      (fields
        (field (name "BOM_Manufacturer Part") "0603WAF220KT5E")
        (field (name "BOM_Supplier Part") "C22939")
      )
      (libsource (lib "") (part "0603WAF220KT5E"))
    )
    (comp (ref "R52")
      (value "2.2")
      (fields
        (field (name "BOM_Manufacturer Part") "0603WAF220KT5E")
        (field (name "BOM_Supplier Part") "C22939")
      )
      (libsource (lib "") (part "0603WAF220KT5E"))
    )
    (comp (ref "R54")
      (value "20")
      (fields
        (field (name "BOM_Manufacturer Part") "0603WAF200JT5E")
        (field (name "BOM_Supplier Part") "C22950")
      )
      (libsource (lib "") (part "0603WAF200JT5E"))
    )
    (comp (ref "R55")
      (value "20")
      (fields
        (field (name "BOM_Manufacturer Part") "0603WAF200JT5E")
        (field (name "BOM_Supplier Part") "C22950")
      )
      (libsource (lib "") (part "0603WAF200JT5E"))
    )
    (comp (ref "R60")
      (value "20")
      (fields
        (field (name "BOM_Manufacturer Part") "0603WAF200JT5E")
        (field (name "BOM_Supplier Part") "C22950")
      )
      (libsource (lib "") (part "0603WAF200JT5E"))
    )
    (comp (ref "R61")
      (value "20")
      (fields
        (field (name "BOM_Manufacturer Part") "0603WAF200JT5E")
        (field (name "BOM_Supplier Part") "C22950")
      )
      (libsource (lib "") (part "0603WAF200JT5E"))
    )
    (comp (ref "R63")
      (value "1K")
      (fields
        (field (name "BOM_Manufacturer Part") "1206W4F1001T5E")
        (field (name "BOM_Supplier Part") "C4410")
      )
      (libsource (lib "") (part "1206W4F1001T5E"))
    )
    (comp (ref "R64")
      (value "1K")
      (fields
        (field (name "BOM_Manufacturer Part") "1206W4F1001T5E")
        (field (name "BOM_Supplier Part") "C4410")
      )
      (libsource (lib "") (part "1206W4F1001T5E"))
    )
    (comp (ref "R67")
      (value "10K")
      (fields
        (field (name "BOM_Manufacturer Part") "0805W8F1002T5E")
        (field (name "BOM_Supplier Part") "C17414")
      )
      (libsource (lib "") (part "0805W8F1002T5E_1"))
    )
    (comp (ref "R68")
      (value "10K")
      (fields
        (field (name "BOM_Manufacturer Part") "0805W8F1002T5E")
        (field (name "BOM_Supplier Part") "C17414")
      )
      (libsource (lib "") (part "0805W8F1002T5E_1"))
    )
    (comp (ref "R69")
      (value "0.1")
      (fields
        (field (name "BOM_Manufacturer Part") "MRF6432(2512)LR100FTS")
        (field (name "BOM_Supplier Part") "C76254")
      )
      (libsource (lib "") (part "MRF6432(2512)LR100FTS"))
    )
    (comp (ref "R70")
      (value "0.1")
      (fields
        (field (name "BOM_Manufacturer Part") "MRF6432(2512)LR100FTS")
        (field (name "BOM_Supplier Part") "C76254")
      )
      (libsource (lib "") (part "MRF6432(2512)LR100FTS"))
    )
    (comp (ref "R71")
      (value "10K")
      (fields
        (field (name "BOM_Manufacturer Part") "0805W8F1002T5E")
        (field (name "BOM_Supplier Part") "C17414")
      )
      (libsource (lib "") (part "0805W8F1002T5E_1"))
    )
    (comp (ref "R72")
      (value "10K")
      (fields
        (field (name "BOM_Manufacturer Part") "0805W8F1002T5E")
        (field (name "BOM_Supplier Part") "C17414")
      )
      (libsource (lib "") (part "0805W8F1002T5E_1"))
    )
    (comp (ref "VD1")
      (value "SS14")
      (fields (field (name "BOM_Supplier Part") "C2480"))
      (libsource (lib "") (part "SS14"))
    )
    (comp (ref "VD2")
      (value "SS14")
      (fields (field (name "BOM_Supplier Part") "C2480"))
      (libsource (lib "") (part "SS14"))
    )
    (comp (ref "VD3")
      (value "SS14")
      (fields (field (name "BOM_Supplier Part") "C2480"))
      (libsource (lib "") (part "SS14"))
    )
    (comp (ref "VD4")
      (value "SS14")
      (fields (field (name "BOM_Supplier Part") "C2480"))
      (libsource (lib "") (part "SS14"))
    )
    (comp (ref "VD5")
      (value "SS14")
      (fields (field (name "BOM_Supplier Part") "C2480"))
      (libsource (lib "") (part "SS14"))
    )
    (comp (ref "VD6")
      (value "SS14")
      (fields (field (name "BOM_Supplier Part") "C2480"))
      (libsource (lib "") (part "SS14"))
    )
    (comp (ref "VD7")
      (value "SS54_C22452")
      (fields (field (name "BOM_Manufacturer Part") "SS54") (field (name "BOM_Supplier Part") "C22452"))
      (libsource (lib "") (part "SS54_C22452"))
    )
    (comp (ref "VD8")
      (value "SS54_C22452")
      (fields (field (name "BOM_Manufacturer Part") "SS54") (field (name "BOM_Supplier Part") "C22452"))
      (libsource (lib "") (part "SS54_C22452"))
    )
    (comp (ref "VD9")
      (value "SS54_C22452")
      (fields (field (name "BOM_Manufacturer Part") "SS54") (field (name "BOM_Supplier Part") "C22452"))
      (libsource (lib "") (part "SS54_C22452"))
    )
    (comp (ref "VT1")
      (value "IRF3205ZPBF")
      (fields (field (name "BOM_Supplier Part") "C2612"))
      (libsource (lib "") (part "IRF3205ZPBF"))
    )
    (comp (ref "VT2")
      (value "IRF3205ZPBF")
      (fields (field (name "BOM_Supplier Part") "C2612"))
      (libsource (lib "") (part "IRF3205ZPBF"))
    )
    (comp (ref "VT3")
      (value "IRF3205ZPBF")
      (fields (field (name "BOM_Supplier Part") "C2612"))
      (libsource (lib "") (part "IRF3205ZPBF_1"))
    )
    (comp (ref "VT4")
      (value "IRF3205ZPBF")
      (fields (field (name "BOM_Supplier Part") "C2612"))
      (libsource (lib "") (part "IRF3205ZPBF_1"))
    )
    (comp (ref "VT5")
      (value "IRF3205ZPBF")
      (fields (field (name "BOM_Supplier Part") "C2612"))
      (libsource (lib "") (part "IRF3205ZPBF"))
    )
    (comp (ref "VT6")
      (value "IRF3205ZPBF")
      (fields (field (name "BOM_Supplier Part") "C2612"))
      (libsource (lib "") (part "IRF3205ZPBF"))
    )
    (comp (ref "VT7")
      (value "IRF3205ZPBF")
      (fields (field (name "BOM_Supplier Part") "C2612"))
      (libsource (lib "") (part "IRF3205ZPBF"))
    )
    (comp (ref "VT8")
      (value "IRF3205ZPBF")
      (fields (field (name "BOM_Supplier Part") "C2612"))
      (libsource (lib "") (part "IRF3205ZPBF"))
    )
    (comp (ref "VT9")
      (value "IRF3205ZPBF")
      (fields (field (name "BOM_Supplier Part") "C2612"))
      (libsource (lib "") (part "IRF3205ZPBF"))
    )
    (comp (ref "VT10")
      (value "IRF3205ZPBF")
      (fields (field (name "BOM_Supplier Part") "C2612"))
      (libsource (lib "") (part "IRF3205ZPBF"))
    )
    (comp (ref "VT11")
      (value "IRF3205ZPBF")
      (fields (field (name "BOM_Supplier Part") "C2612"))
      (libsource (lib "") (part "IRF3205ZPBF_1"))
    )
    (comp (ref "VT13")
      (value "IRF3205ZPBF")
      (fields (field (name "BOM_Supplier Part") "C2612"))
      (libsource (lib "") (part "IRF3205ZPBF_1"))
    )
    (comp (ref "VT14")
      (value "IRF3205ZPBF")
      (fields (field (name "BOM_Supplier Part") "C2612"))
      (libsource (lib "") (part "IRF3205ZPBF_1"))
    )
    (comp (ref "VT15")
      (value "IRF3205ZPBF")
      (fields (field (name "BOM_Supplier Part") "C2612"))
      (libsource (lib "") (part "IRF3205ZPBF_1"))
    )
    (comp (ref "VT16")
      (value "IRF3205ZPBF")
      (fields (field (name "BOM_Supplier Part") "C2612"))
      (libsource (lib "") (part "IRF3205ZPBF_1"))
    )
    (comp (ref "VT17")
      (value "IRF3205ZPBF")
      (fields (field (name "BOM_Supplier Part") "C2612"))
      (libsource (lib "") (part "IRF3205ZPBF_1"))
    )
    (comp (ref "VT18")
      (value "IRF9620PBF")
      (fields (field (name "BOM_Supplier Part") "C145334"))
      (libsource (lib "") (part "IRF9620PBF_1"))
    )
    (comp (ref "VT19")
      (value "IRF9620PBF")
      (fields (field (name "BOM_Supplier Part") "C145334"))
      (libsource (lib "") (part "IRF9620PBF"))
    )
    (comp (ref "VT20")
      (value "IRLML2803TRPBF")
      (fields (field (name "BOM_Supplier Part") "C2590"))
      (libsource (lib "") (part "IRLML2803TRPBF_1"))
    )
    (comp (ref "VT21")
      (value "IRLML2803TRPBF")
      (fields (field (name "BOM_Supplier Part") "C2590"))
      (libsource (lib "") (part "IRLML2803TRPBF"))
    )
    (comp (ref "VT22")
      (value "IRF3205ZPBF")
      (fields (field (name "BOM_Supplier Part") "C2612"))
      (libsource (lib "") (part "IRF3205ZPBF"))
    )
    (comp (ref "VT23")
      (value "IRF3205ZPBF")
      (fields (field (name "BOM_Supplier Part") "C2612"))
      (libsource (lib "") (part "IRF3205ZPBF_1"))
    )
    (comp (ref "C33")
      (value "10uF")
      (fields
        (field (name "BOM_Manufacturer Part") "CL31A106KBHNNNE")
        (field (name "BOM_Supplier Part") "C13585")
      )
      (libsource (lib "") (part "CL31A106KBHNNNE"))
    )
    (comp (ref "C34")
      (value "10uF")
      (fields
        (field (name "BOM_Manufacturer Part") "CL31A106KBHNNNE")
        (field (name "BOM_Supplier Part") "C13585")
      )
      (libsource (lib "") (part "CL31A106KBHNNNE"))
    )
    (comp (ref "C42")
      (value "10uF")
      (fields
        (field (name "BOM_Manufacturer Part") "CL31A106KBHNNNE")
        (field (name "BOM_Supplier Part") "C13585")
      )
      (libsource (lib "") (part "CL31A106KBHNNNE"))
    )
    (comp (ref "C43")
      (value "10uF")
      (fields
        (field (name "BOM_Manufacturer Part") "CL31A106KBHNNNE")
        (field (name "BOM_Supplier Part") "C13585")
      )
      (libsource (lib "") (part "CL31A106KBHNNNE"))
    )
    (comp (ref "C44")
      (value "10uF")
      (fields
        (field (name "BOM_Manufacturer Part") "CL31A106KBHNNNE")
        (field (name "BOM_Supplier Part") "C13585")
      )
      (libsource (lib "") (part "CL31A106KBHNNNE"))
    )
    (comp (ref "C45")
      (value "10uF")
      (fields
        (field (name "BOM_Manufacturer Part") "CL31A106KBHNNNE")
        (field (name "BOM_Supplier Part") "C13585")
      )
      (libsource (lib "") (part "CL31A106KBHNNNE"))
    )
    (comp (ref "C46")
      (value "10uF")
      (fields
        (field (name "BOM_Manufacturer Part") "CL31A106KBHNNNE")
        (field (name "BOM_Supplier Part") "C13585")
      )
      (libsource (lib "") (part "CL31A106KBHNNNE"))
    )
    (comp (ref "C47")
      (value "10uF")
      (fields
        (field (name "BOM_Manufacturer Part") "CL31A106KBHNNNE")
        (field (name "BOM_Supplier Part") "C13585")
      )
      (libsource (lib "") (part "CL31A106KBHNNNE"))
    )
    (comp (ref "C48")
      (value "10uF")
      (fields
        (field (name "BOM_Manufacturer Part") "CL31A106KBHNNNE")
        (field (name "BOM_Supplier Part") "C13585")
      )
      (libsource (lib "") (part "CL31A106KBHNNNE"))
    )
    (comp (ref "C49")
      (value "10uF")
      (fields
        (field (name "BOM_Manufacturer Part") "CL31A106KBHNNNE")
        (field (name "BOM_Supplier Part") "C13585")
      )
      (libsource (lib "") (part "CL31A106KBHNNNE"))
    )
    (comp (ref "C50")
      (value "100nF")
      (fields
        (field (name "BOM_Manufacturer Part") "CC0805KRX7R9BB104")
        (field (name "BOM_Supplier Part") "C49678")
      )
      (libsource (lib "") (part "CC0805KRX7R9BB104"))
    )
    (comp (ref "C51")
      (value "100nF")
      (fields
        (field (name "BOM_Manufacturer Part") "CC0805KRX7R9BB104")
        (field (name "BOM_Supplier Part") "C49678")
      )
      (libsource (lib "") (part "CC0805KRX7R9BB104"))
    )
    (comp (ref "C52")
      (value "100nF")
      (fields
        (field (name "BOM_Manufacturer Part") "CC0805KRX7R9BB104")
        (field (name "BOM_Supplier Part") "C49678")
      )
      (libsource (lib "") (part "CC0805KRX7R9BB104"))
    )
    (comp (ref "C58")
      (value "100nF")
      (fields
        (field (name "BOM_Manufacturer Part") "CC0805KRX7R9BB104")
        (field (name "BOM_Supplier Part") "C49678")
      )
      (libsource (lib "") (part "CC0805KRX7R9BB104"))
    )
    (comp (ref "C59")
      (value "100nF")
      (fields
        (field (name "BOM_Manufacturer Part") "CC0805KRX7R9BB104")
        (field (name "BOM_Supplier Part") "C49678")
      )
      (libsource (lib "") (part "CC0805KRX7R9BB104"))
    )
    (comp (ref "D15")
      (value "UCC27519DBVR")
      (fields (field (name "BOM_Supplier Part") "C93674"))
      (libsource (lib "") (part "UCC27519DBVR"))
    )
    (comp (ref "D16")
      (value "UCC27519DBVR")
      (fields (field (name "BOM_Supplier Part") "C93674"))
      (libsource (lib "") (part "UCC27519DBVR"))
    )
    (comp (ref "D17")
      (value "UCC27519DBVR")
      (fields (field (name "BOM_Supplier Part") "C93674"))
      (libsource (lib "") (part "UCC27519DBVR"))
    )
    (comp (ref "D18")
      (value "UCC27519DBVR")
      (fields (field (name "BOM_Supplier Part") "C93674"))
      (libsource (lib "") (part "UCC27519DBVR"))
    )
    (comp (ref "D19")
      (value "SN74LVC2G04DBVR")
      (fields (field (name "BOM_Supplier Part") "C10428"))
      (libsource (lib "") (part "SN74LVC2G04DBVR"))
    )
    (comp (ref "P2")
      (value "Header-Male-2.54_1x1")
      (fields (field (name "BOM_Supplier Part") "C81276"))
      (libsource (lib "") (part "Header-Male-2.54_1x1_1"))
    )
    (comp (ref "P3")
      (value "Header-Male-2.54_1x1")
      (fields (field (name "BOM_Supplier Part") "C81276"))
      (libsource (lib "") (part "Header-Male-2.54_1x1_1"))
    )
    (comp (ref "P23")
      (value "Header-Male-2.54_1x1")
      (fields (field (name "BOM_Supplier Part") "C81276"))
      (libsource (lib "") (part "Header-Male-2.54_1x1_1"))
    )
    (comp (ref "P24")
      (value "Header-Male-2.54_1x1")
      (fields (field (name "BOM_Supplier Part") "C81276"))
      (libsource (lib "") (part "Header-Male-2.54_1x1_1"))
    )
    (comp (ref "P25")
      (value "Header-Male-2.54_1x1")
      (fields (field (name "BOM_Supplier Part") "C81276"))
      (libsource (lib "") (part "Header-Male-2.54_1x1_1"))
    )
    (comp (ref "P26")
      (value "Header-Male-2.54_1x1")
      (fields (field (name "BOM_Supplier Part") "C81276"))
      (libsource (lib "") (part "Header-Male-2.54_1x1_1"))
    )
    (comp (ref "P27")
      (value "Header-Male-2.54_1x1")
      (fields (field (name "BOM_Supplier Part") "C81276"))
      (libsource (lib "") (part "Header-Male-2.54_1x1_1"))
    )
    (comp (ref "P28")
      (value "Header-Male-2.54_1x1")
      (fields (field (name "BOM_Supplier Part") "C81276"))
      (libsource (lib "") (part "Header-Male-2.54_1x1_1"))
    )
    (comp (ref "P29")
      (value "Header-Male-2.54_1x1")
      (fields (field (name "BOM_Supplier Part") "C81276"))
      (libsource (lib "") (part "Header-Male-2.54_1x1_1"))
    )
    (comp (ref "P30")
      (value "Header-Male-2.54_1x1")
      (fields (field (name "BOM_Supplier Part") "C81276"))
      (libsource (lib "") (part "Header-Male-2.54_1x1_1"))
    )
    (comp (ref "P31")
      (value "Header-Male-2.54_1x1")
      (fields (field (name "BOM_Supplier Part") "C81276"))
      (libsource (lib "") (part "Header-Male-2.54_1x1_1"))
    )
    (comp (ref "P60")
      (value "Header-Male-2.54_1x1")
      (fields (field (name "BOM_Supplier Part") "C81276"))
      (libsource (lib "") (part "Header-Male-2.54_1x1_1"))
    )
    (comp (ref "P61")
      (value "Header-Male-2.54_1x1")
      (fields (field (name "BOM_Supplier Part") "C81276"))
      (libsource (lib "") (part "Header-Male-2.54_1x1"))
    )
    (comp (ref "P62")
      (value "Header-Male-2.54_1x1")
      (fields (field (name "BOM_Supplier Part") "C81276"))
      (libsource (lib "") (part "Header-Male-2.54_1x1"))
    )
    (comp (ref "P63")
      (value "Header-Male-2.54_1x1")
      (fields (field (name "BOM_Supplier Part") "C81276"))
      (libsource (lib "") (part "Header-Male-2.54_1x1"))
    )
    (comp (ref "P64")
      (value "Header-Male-2.54_1x1")
      (fields (field (name "BOM_Supplier Part") "C81276"))
      (libsource (lib "") (part "Header-Male-2.54_1x1"))
    )
    (comp (ref "P65")
      (value "Header-Male-2.54_1x1")
      (fields (field (name "BOM_Supplier Part") "C81276"))
      (libsource (lib "") (part "Header-Male-2.54_1x1"))
    )
    (comp (ref "P66")
      (value "Header-Male-2.54_1x1")
      (fields (field (name "BOM_Supplier Part") "C81276"))
      (libsource (lib "") (part "Header-Male-2.54_1x1"))
    )
    (comp (ref "P67")
      (value "Header-Male-2.54_1x1")
      (fields (field (name "BOM_Supplier Part") "C81276"))
      (libsource (lib "") (part "Header-Male-2.54_1x1_1"))
    )
    (comp (ref "P68")
      (value "Header-Male-2.54_1x1")
      (fields (field (name "BOM_Supplier Part") "C81276"))
      (libsource (lib "") (part "Header-Male-2.54_1x1_1"))
    )
    (comp (ref "P69")
      (value "Header-Male-2.54_1x1")
      (fields (field (name "BOM_Supplier Part") "C81276"))
      (libsource (lib "") (part "Header-Male-2.54_1x1_1"))
    )
    (comp (ref "P70")
      (value "Header-Male-2.54_1x1")
      (fields (field (name "BOM_Supplier Part") "C81276"))
      (libsource (lib "") (part "Header-Male-2.54_1x1_1"))
    )
    (comp (ref "P71")
      (value "Header-Male-2.54_1x1")
      (fields (field (name "BOM_Supplier Part") "C81276"))
      (libsource (lib "") (part "Header-Male-2.54_1x1_1"))
    )
    (comp (ref "P72")
      (value "Header-Male-2.54_1x1")
      (fields (field (name "BOM_Supplier Part") "C81276"))
      (libsource (lib "") (part "Header-Male-2.54_1x1_1"))
    )
    (comp (ref "P73")
      (value "Header-Male-2.54_1x1")
      (fields (field (name "BOM_Supplier Part") "C81276"))
      (libsource (lib "") (part "Header-Male-2.54_1x1"))
    )
    (comp (ref "P74")
      (value "Header-Male-2.54_1x1")
      (fields (field (name "BOM_Supplier Part") "C81276"))
      (libsource (lib "") (part "Header-Male-2.54_1x1"))
    )
    (comp (ref "P75")
      (value "Header-Male-2.54_1x1")
      (fields (field (name "BOM_Supplier Part") "C81276"))
      (libsource (lib "") (part "Header-Male-2.54_1x1"))
    )
    (comp (ref "P76")
      (value "Header-Male-2.54_1x1")
      (fields (field (name "BOM_Supplier Part") "C81276"))
      (libsource (lib "") (part "Header-Male-2.54_1x1"))
    )
    (comp (ref "P77")
      (value "Header-Male-2.54_1x1")
      (fields (field (name "BOM_Supplier Part") "C81276"))
      (libsource (lib "") (part "Header-Male-2.54_1x1"))
    )
    (comp (ref "P78")
      (value "Header-Male-2.54_1x1")
      (fields (field (name "BOM_Supplier Part") "C81276"))
      (libsource (lib "") (part "Header-Male-2.54_1x1"))
    )
    (comp (ref "R28")
      (value "8.2K")
      (fields
        (field (name "BOM_Manufacturer Part") "0805W8F8201T5E")
        (field (name "BOM_Supplier Part") "C17828")
      )
      (libsource (lib "") (part "0805W8F8201T5E"))
    )
    (comp (ref "R29")
      (value "2K")
      (fields
        (field (name "BOM_Manufacturer Part") "0805W8F2001T5E")
        (field (name "BOM_Supplier Part") "C17604")
      )
      (libsource (lib "") (part "0805W8F2001T5E"))
    )
    (comp (ref "R40")
      (value "2.2")
      (fields
        (field (name "BOM_Manufacturer Part") "0603WAF220KT5E")
        (field (name "BOM_Supplier Part") "C22939")
      )
      (libsource (lib "") (part "0603WAF220KT5E"))
    )
    (comp (ref "R41")
      (value "10K")
      (fields
        (field (name "BOM_Manufacturer Part") "0805W8F1002T5E")
        (field (name "BOM_Supplier Part") "C17414")
      )
      (libsource (lib "") (part "0805W8F1002T5E"))
    )
    (comp (ref "R42")
      (value "2.2")
      (fields
        (field (name "BOM_Manufacturer Part") "0603WAF220KT5E")
        (field (name "BOM_Supplier Part") "C22939")
      )
      (libsource (lib "") (part "0603WAF220KT5E"))
    )
    (comp (ref "R43")
      (value "10K")
      (fields
        (field (name "BOM_Manufacturer Part") "0805W8F1002T5E")
        (field (name "BOM_Supplier Part") "C17414")
      )
      (libsource (lib "") (part "0805W8F1002T5E_1"))
    )
    (comp (ref "R44")
      (value "10K")
      (fields
        (field (name "BOM_Manufacturer Part") "0805W8F1002T5E")
        (field (name "BOM_Supplier Part") "C17414")
      )
      (libsource (lib "") (part "0805W8F1002T5E_1"))
    )
    (comp (ref "R53")
      (value "2.2")
      (fields
        (field (name "BOM_Manufacturer Part") "0603WAF220KT5E")
        (field (name "BOM_Supplier Part") "C22939")
      )
      (libsource (lib "") (part "0603WAF220KT5E_1"))
    )
    (comp (ref "R56")
      (value "10K")
      (fields
        (field (name "BOM_Manufacturer Part") "0805W8F1002T5E")
        (field (name "BOM_Supplier Part") "C17414")
      )
      (libsource (lib "") (part "0805W8F1002T5E"))
    )
    (comp (ref "R57")
      (value "2.2")
      (fields
        (field (name "BOM_Manufacturer Part") "0603WAF220KT5E")
        (field (name "BOM_Supplier Part") "C22939")
      )
      (libsource (lib "") (part "0603WAF220KT5E_1"))
    )
    (comp (ref "R58")
      (value "10K")
      (fields
        (field (name "BOM_Manufacturer Part") "0603WAF1002T5E")
        (field (name "BOM_Supplier Part") "C25804")
      )
      (libsource (lib "") (part "0603WAF1002T5E_1"))
    )
    (comp (ref "R65")
      (value "10K")
      (fields
        (field (name "BOM_Manufacturer Part") "0603WAF1002T5E")
        (field (name "BOM_Supplier Part") "C25804")
      )
      (libsource (lib "") (part "0603WAF1002T5E"))
    )
    (comp (ref "R66")
      (value "20")
      (fields
        (field (name "BOM_Manufacturer Part") "0603WAF200JT5E")
        (field (name "BOM_Supplier Part") "C22950")
      )
      (libsource (lib "") (part "0603WAF200JT5E"))
    )
    (comp (ref "R73")
      (value "20")
      (fields
        (field (name "BOM_Manufacturer Part") "0603WAF200JT5E")
        (field (name "BOM_Supplier Part") "C22950")
      )
      (libsource (lib "") (part "0603WAF200JT5E"))
    )
    (comp (ref "VD10")
      (value "DSA90C200HB")
      (fields (field (name "BOM_Supplier Part") "C480636"))
      (libsource (lib "") (part "DSA90C200HB_1"))
    )
    (comp (ref "VD11")
      (value "DSA90C200HB")
      (fields (field (name "BOM_Supplier Part") "C480636"))
      (libsource (lib "") (part "DSA90C200HB"))
    )
    (comp (ref "VD12")
      (value "DSA90C200HB")
      (fields (field (name "BOM_Supplier Part") "C480636"))
      (libsource (lib "") (part "DSA90C200HB"))
    )
    (comp (ref "VD13")
      (value "DSA90C200HB")
      (fields (field (name "BOM_Supplier Part") "C480636"))
      (libsource (lib "") (part "DSA90C200HB_1"))
    )
    (comp (ref "VT24")
      (value "IRF3205ZPBF")
      (fields (field (name "BOM_Supplier Part") "C2612"))
      (libsource (lib "") (part "IRF3205ZPBF"))
    )
    (comp (ref "VT25")
      (value "IRF3205ZPBF")
      (fields (field (name "BOM_Supplier Part") "C2612"))
      (libsource (lib "") (part "IRF3205ZPBF"))
    )
    (comp (ref "VT26")
      (value "IRF3205ZPBF")
      (fields (field (name "BOM_Supplier Part") "C2612"))
      (libsource (lib "") (part "IRF3205ZPBF_1"))
    )
    (comp (ref "VT27")
      (value "IRF3205ZPBF")
      (fields (field (name "BOM_Supplier Part") "C2612"))
      (libsource (lib "") (part "IRF3205ZPBF_1"))
    )
    (comp (ref "VT28")
      (value "IRF9620PBF")
      (fields (field (name "BOM_Supplier Part") "C145334"))
      (libsource (lib "") (part "IRF9620PBF"))
    )
    (comp (ref "VT29")
      (value "IRF9620PBF")
      (fields (field (name "BOM_Supplier Part") "C145334"))
      (libsource (lib "") (part "IRF9620PBF"))
    )
    (comp (ref "VT30")
      (value "IRF9620PBF")
      (fields (field (name "BOM_Supplier Part") "C145334"))
      (libsource (lib "") (part "IRF9620PBF_1"))
    )
    (comp (ref "VT31")
      (value "IRF9620PBF")
      (fields (field (name "BOM_Supplier Part") "C145334"))
      (libsource (lib "") (part "IRF9620PBF_1"))
    )
    (comp (ref "C14")
      (value "100nF")
      (fields
        (field (name "BOM_Manufacturer Part") "CT41G-0805-2X1-50V-0.1uF-K(N)")
        (field (name "BOM_Supplier Part") "C126469")
      )
      (libsource (lib "") (part "CT41G-0805-2X1-50V-0.1UF-K(N)"))
    )
    (comp (ref "C15")
      (value "100nF")
      (fields
        (field (name "BOM_Manufacturer Part") "CT41G-0805-2X1-50V-0.1uF-K(N)")
        (field (name "BOM_Supplier Part") "C126469")
      )
      (libsource (lib "") (part "CT41G-0805-2X1-50V-0.1UF-K(N)"))
    )
    (comp (ref "C16")
      (value "4.7uF")
      (fields
        (field (name "BOM_Manufacturer Part") "C2012X7R1A475KT000N")
        (field (name "BOM_Supplier Part") "C76639")
      )
      (libsource (lib "") (part "C2012X7R1A475KT000N_1"))
    )
    (comp (ref "C17")
      (value "100nF")
      (fields
        (field (name "BOM_Manufacturer Part") "CT41G-0805-2X1-50V-0.1uF-K(N)")
        (field (name "BOM_Supplier Part") "C126469")
      )
      (libsource (lib "") (part "CT41G-0805-2X1-50V-0.1UF-K(N)"))
    )
    (comp (ref "C53")
      (value "100nF")
      (fields
        (field (name "BOM_Manufacturer Part") "CT41G-0805-2X1-50V-0.1uF-K(N)")
        (field (name "BOM_Supplier Part") "C126469")
      )
      (libsource (lib "") (part "CT41G-0805-2X1-50V-0.1UF-K(N)"))
    )
    (comp (ref "C54")
      (value "4.7uF")
      (fields
        (field (name "BOM_Manufacturer Part") "C2012X7R1A475KT000N")
        (field (name "BOM_Supplier Part") "C76639")
      )
      (libsource (lib "") (part "C2012X7R1A475KT000N"))
    )
    (comp (ref "C55")
      (value "100nF")
      (fields
        (field (name "BOM_Manufacturer Part") "CT41G-0805-2X1-50V-0.1uF-K(N)")
        (field (name "BOM_Supplier Part") "C126469")
      )
      (libsource (lib "") (part "CT41G-0805-2X1-50V-0.1UF-K(N)_1"))
    )
    (comp (ref "C56")
      (value "100nF")
      (fields
        (field (name "BOM_Manufacturer Part") "CT41G-0805-2X1-50V-0.1uF-K(N)")
        (field (name "BOM_Supplier Part") "C126469")
      )
      (libsource (lib "") (part "CT41G-0805-2X1-50V-0.1UF-K(N)_1"))
    )
    (comp (ref "L5")
      (value "220Ω")
      (fields
        (field (name "BOM_Manufacturer Part") "BLM21PG221SH1D")
        (field (name "BOM_Supplier Part") "C88994")
      )
      (libsource (lib "") (part "BLM21PG221SH1D"))
    )
    (comp (ref "LED1")
      (value "17-21/R6C-AQ2R2B/3T")
      (fields (field (name "BOM_Supplier Part") "C113551"))
      (libsource (lib "") (part "17-21/R6C-AQ2R2B/3T"))
    )
    (comp (ref "LED2")
      (value "17-21/R6C-AQ2R2B/3T")
      (fields (field (name "BOM_Supplier Part") "C113551"))
      (libsource (lib "") (part "17-21/R6C-AQ2R2B/3T"))
    )
    (comp (ref "R45")
      (value "100")
      (fields
        (field (name "BOM_Manufacturer Part") "RC0805JR-7W100RL")
        (field (name "BOM_Supplier Part") "C309572")
      )
      (libsource (lib "") (part "RC0805JR-7W100RL"))
    )
    (comp (ref "R46")
      (value "100")
      (fields
        (field (name "BOM_Manufacturer Part") "RC0805JR-7W100RL")
        (field (name "BOM_Supplier Part") "C309572")
      )
      (libsource (lib "") (part "RC0805JR-7W100RL"))
    )
    (comp (ref "R47")
      (value "1K")
      (fields
        (field (name "BOM_Manufacturer Part") "RM10JTN102")
        (field (name "BOM_Supplier Part") "C113195")
      )
      (libsource (lib "") (part "RM10JTN102"))
    )
    (comp (ref "R48")
      (value "1K")
      (fields
        (field (name "BOM_Manufacturer Part") "RM10JTN102")
        (field (name "BOM_Supplier Part") "C113195")
      )
      (libsource (lib "") (part "RM10JTN102"))
    )
    (comp (ref "R49")
      (value "10K")
      (fields
        (field (name "BOM_Manufacturer Part") "CR-05FL7---10K")
        (field (name "BOM_Supplier Part") "C416062")
      )
      (libsource (lib "") (part "CR-05FL7---10K"))
    )
    (comp (ref "R50")
      (value "4.7K")
      (fields
        (field (name "BOM_Manufacturer Part") "RMC08054.7K5%N")
        (field (name "BOM_Supplier Part") "C269733")
      )
      (libsource (lib "") (part "RMC08054.7K5%N"))
    )
    (comp (ref "U1")
      (value "FT232RL-REEL")
      (fields (field (name "BOM_Supplier Part") "C8690"))
      (libsource (lib "") (part "FT232RL-REEL"))
    )
    (comp (ref "U4") (value "ISO7221BD") (libsource (lib "") (part "ISO7221BD")))
    (comp (ref "USB1")
      (value "BF 90°")
      (fields (field (name "BOM_Supplier Part") "C456014"))
      (libsource (lib "") (part "BF 90°"))
    )
    (comp (ref "B1")
      (value "HCM1203X")
      (fields (field (name "BOM_Supplier Part") "https://www.chipdip.ru/product/hcm1203x"))
      (libsource (lib "") (part "HCM1203X"))
    )
    (comp (ref "C13")
      (value "20pF")
      (fields
        (field (name "BOM_Manufacturer Part") "CL10C200JB8NNNC")
        (field (name "BOM_Supplier Part") "C1648")
      )
      (libsource (lib "") (part "CL10C200JB8NNNC"))
    )
    (comp (ref "C28")
      (value "100nF")
      (fields
        (field (name "BOM_Manufacturer Part") "CT41G-0805-2X1-50V-0.1uF-K(N)")
        (field (name "BOM_Supplier Part") "C126469")
      )
      (libsource (lib "") (part "CT41G-0805-2X1-50V-0.1UF-K(N)"))
    )
    (comp (ref "C29")
      (value "100nF")
      (fields
        (field (name "BOM_Manufacturer Part") "CT41G-0805-2X1-50V-0.1uF-K(N)")
        (field (name "BOM_Supplier Part") "C126469")
      )
      (libsource (lib "") (part "CT41G-0805-2X1-50V-0.1UF-K(N)"))
    )
    (comp (ref "C30")
      (value "1uF")
      (fields
        (field (name "BOM_Manufacturer Part") "CL21B105KAFNFNE")
        (field (name "BOM_Supplier Part") "C1712")
      )
      (libsource (lib "") (part "CL21B105KAFNFNE"))
    )
    (comp (ref "C31")
      (value "100nF")
      (fields
        (field (name "BOM_Manufacturer Part") "CT41G-0805-2X1-50V-0.1uF-K(N)")
        (field (name "BOM_Supplier Part") "C126469")
      )
      (libsource (lib "") (part "CT41G-0805-2X1-50V-0.1UF-K(N)"))
    )
    (comp (ref "C32")
      (value "4.7uF")
      (fields
        (field (name "BOM_Manufacturer Part") "C2012X7R1A475KT000N")
        (field (name "BOM_Supplier Part") "C76639")
      )
      (libsource (lib "") (part "C2012X7R1A475KT000N"))
    )
    (comp (ref "C35")
      (value "100nF")
      (fields
        (field (name "BOM_Manufacturer Part") "CT41G-0805-2X1-50V-0.1uF-K(N)")
        (field (name "BOM_Supplier Part") "C126469")
      )
      (libsource (lib "") (part "CT41G-0805-2X1-50V-0.1UF-K(N)"))
    )
    (comp (ref "C36")
      (value "100nF")
      (fields
        (field (name "BOM_Manufacturer Part") "CT41G-0805-2X1-50V-0.1uF-K(N)")
        (field (name "BOM_Supplier Part") "C126469")
      )
      (libsource (lib "") (part "CT41G-0805-2X1-50V-0.1UF-K(N)"))
    )
    (comp (ref "C37") (value "100u") (libsource (lib "") (part "Cap_Tantalum(SMD)_D-7343_EU")))
    (comp (ref "C38")
      (value "20pF")
      (fields
        (field (name "BOM_Manufacturer Part") "CL10C200JB8NNNC")
        (field (name "BOM_Supplier Part") "C1648")
      )
      (libsource (lib "") (part "CL10C200JB8NNNC"))
    )
    (comp (ref "C39")
      (value "12pF")
      (fields
        (field (name "BOM_Manufacturer Part") "CL10C120JB8NNNC")
        (field (name "BOM_Supplier Part") "C38523")
      )
      (libsource (lib "") (part "CL10C120JB8NNNC"))
    )
    (comp (ref "C40")
      (value "12pF")
      (fields
        (field (name "BOM_Manufacturer Part") "CL10C120JB8NNNC")
        (field (name "BOM_Supplier Part") "C38523")
      )
      (libsource (lib "") (part "CL10C120JB8NNNC"))
    )
    (comp (ref "C41")
      (value "1uF")
      (fields
        (field (name "BOM_Manufacturer Part") "CL21B105KAFNFNE")
        (field (name "BOM_Supplier Part") "C1712")
      )
      (libsource (lib "") (part "CL21B105KAFNFNE_1"))
    )
    (comp (ref "C61")
      (value "10nF")
      (fields
        (field (name "BOM_Manufacturer Part") "GCM216R71H103KA37D")
        (field (name "BOM_Supplier Part") "C388908")
      )
      (libsource (lib "") (part "GCM216R71H103KA37D"))
    )
    (comp (ref "DA5")
      (value "REG1117-3.3")
      (fields (field (name "BOM_Supplier Part") "C132201"))
      (libsource (lib "") (part "REG1117-3.3"))
    )
    (comp (ref "DD1") (value "STM32F334R8T6") (libsource (lib "") (part "STM32F334R8T6")))
    (comp (ref "H1")
      (value "Header-Male-2.54_1x3")
      (fields
        (field (name "BOM_Manufacturer Part") "Header2.54mm 1*3P")
        (field (name "BOM_Supplier Part") "C49257")
      )
      (libsource (lib "") (part "Header-Male-2.54_1x3"))
    )
    (comp (ref "H3")
      (value "Header-Male-2.54_1x3")
      (fields
        (field (name "BOM_Manufacturer Part") "Header2.54mm 1*3P")
        (field (name "BOM_Supplier Part") "C49257")
      )
      (libsource (lib "") (part "Header-Male-2.54_1x3"))
    )
    (comp (ref "L1")
      (value "1uH")
      (fields
        (field (name "BOM_Manufacturer Part") "SDFL2012Q1R0KTF")
        (field (name "BOM_Supplier Part") "C1042")
      )
      (libsource (lib "") (part "SDFL2012Q1R0KTF"))
    )
    (comp (ref "L2")
      (value "1uH")
      (fields
        (field (name "BOM_Manufacturer Part") "SDFL2012Q1R0KTF")
        (field (name "BOM_Supplier Part") "C1042")
      )
      (libsource (lib "") (part "SDFL2012Q1R0KTF_1"))
    )
    (comp (ref "P1")
      (value "WJ2EDGVC-5.08-2P")
      (fields (field (name "BOM_Supplier Part") "C8445"))
      (libsource (lib "") (part "WJ2EDGVC-5.08-2P"))
    )
    (comp (ref "P18")
      (value "Header-Male-2.54_1x1")
      (fields (field (name "BOM_Supplier Part") "C81276"))
      (libsource (lib "") (part "Header-Male-2.54_1x1"))
    )
    (comp (ref "P19")
      (value "Header-Male-2.54_1x1")
      (fields (field (name "BOM_Supplier Part") "C81276"))
      (libsource (lib "") (part "Header-Male-2.54_1x1"))
    )
    (comp (ref "P20")
      (value "Header-Male-2.54_1x1")
      (fields (field (name "BOM_Supplier Part") "C81276"))
      (libsource (lib "") (part "Header-Male-2.54_1x1"))
    )
    (comp (ref "P21")
      (value "Header-Male-2.54_1x1")
      (fields (field (name "BOM_Supplier Part") "C81276"))
      (libsource (lib "") (part "Header-Male-2.54_1x1"))
    )
    (comp (ref "P22")
      (value "Header-Male-2.54_1x1")
      (fields (field (name "BOM_Supplier Part") "C81276"))
      (libsource (lib "") (part "Header-Male-2.54_1x1"))
    )
    (comp (ref "Q3")
      (value "8MHz")
      (fields
        (field (name "BOM_Manufacturer Part") "X50328MSB2GI")
        (field (name "BOM_Supplier Part") "C115962")
      )
      (libsource (lib "") (part "X50328MSB2GI"))
    )
    (comp (ref "R3")
      (value "20")
      (fields
        (field (name "BOM_Manufacturer Part") "0603WAF200JT5E")
        (field (name "BOM_Supplier Part") "C22950")
      )
      (libsource (lib "") (part "0603WAF200JT5E"))
    )
    (comp (ref "R4")
      (value "20")
      (fields
        (field (name "BOM_Manufacturer Part") "0603WAF200JT5E")
        (field (name "BOM_Supplier Part") "C22950")
      )
      (libsource (lib "") (part "0603WAF200JT5E"))
    )
    (comp (ref "R5")
      (value "20")
      (fields
        (field (name "BOM_Manufacturer Part") "0603WAF200JT5E")
        (field (name "BOM_Supplier Part") "C22950")
      )
      (libsource (lib "") (part "0603WAF200JT5E"))
    )
    (comp (ref "R6")
      (value "10K")
      (fields
        (field (name "BOM_Manufacturer Part") "CR-05FL7---10K")
        (field (name "BOM_Supplier Part") "C416062")
      )
      (libsource (lib "") (part "CR-05FL7---10K"))
    )
    (comp (ref "R7")
      (value "20")
      (fields
        (field (name "BOM_Manufacturer Part") "0603WAF200JT5E")
        (field (name "BOM_Supplier Part") "C22950")
      )
      (libsource (lib "") (part "0603WAF200JT5E"))
    )
    (comp (ref "R9")
      (value "20")
      (fields
        (field (name "BOM_Manufacturer Part") "0603WAF200JT5E")
        (field (name "BOM_Supplier Part") "C22950")
      )
      (libsource (lib "") (part "0603WAF200JT5E"))
    )
    (comp (ref "R10")
      (value "20")
      (fields
        (field (name "BOM_Manufacturer Part") "0603WAF200JT5E")
        (field (name "BOM_Supplier Part") "C22950")
      )
      (libsource (lib "") (part "0603WAF200JT5E"))
    )
    (comp (ref "R12")
      (value "20")
      (fields
        (field (name "BOM_Manufacturer Part") "0603WAF200JT5E")
        (field (name "BOM_Supplier Part") "C22950")
      )
      (libsource (lib "") (part "0603WAF200JT5E_1"))
    )
    (comp (ref "R13")
      (value "20")
      (fields
        (field (name "BOM_Manufacturer Part") "0603WAF200JT5E")
        (field (name "BOM_Supplier Part") "C22950")
      )
      (libsource (lib "") (part "0603WAF200JT5E_1"))
    )
    (comp (ref "R14")
      (value "20")
      (fields
        (field (name "BOM_Manufacturer Part") "0603WAF200JT5E")
        (field (name "BOM_Supplier Part") "C22950")
      )
      (libsource (lib "") (part "0603WAF200JT5E_1"))
    )
    (comp (ref "R15")
      (value "20")
      (fields
        (field (name "BOM_Manufacturer Part") "0603WAF200JT5E")
        (field (name "BOM_Supplier Part") "C22950")
      )
      (libsource (lib "") (part "0603WAF200JT5E_1"))
    )
    (comp (ref "R30")
      (value "20")
      (fields
        (field (name "BOM_Manufacturer Part") "0603WAF200JT5E")
        (field (name "BOM_Supplier Part") "C22950")
      )
      (libsource (lib "") (part "0603WAF200JT5E"))
    )
    (comp (ref "R31")
      (value "20")
      (fields
        (field (name "BOM_Manufacturer Part") "0603WAF200JT5E")
        (field (name "BOM_Supplier Part") "C22950")
      )
      (libsource (lib "") (part "0603WAF200JT5E"))
    )
    (comp (ref "R33")
      (value "10K")
      (fields
        (field (name "BOM_Manufacturer Part") "CR-05FL7---10K")
        (field (name "BOM_Supplier Part") "C416062")
      )
      (libsource (lib "") (part "CR-05FL7---10K"))
    )
    (comp (ref "R34")
      (value "10K")
      (fields
        (field (name "BOM_Manufacturer Part") "CR-05FL7---10K")
        (field (name "BOM_Supplier Part") "C416062")
      )
      (libsource (lib "") (part "CR-05FL7---10K"))
    )
    (comp (ref "R59")
      (value "20")
      (fields
        (field (name "BOM_Manufacturer Part") "0603WAF200JT5E")
        (field (name "BOM_Supplier Part") "C22950")
      )
      (libsource (lib "") (part "0603WAF200JT5E"))
    )
    (comp (ref "R62")
      (value "20")
      (fields
        (field (name "BOM_Manufacturer Part") "0603WAF200JT5E")
        (field (name "BOM_Supplier Part") "C22950")
      )
      (libsource (lib "") (part "0603WAF200JT5E"))
    )
    (comp (ref "R74")
      (value "2K")
      (fields
        (field (name "BOM_Manufacturer Part") "0805W8F2001T5E")
        (field (name "BOM_Supplier Part") "C17604")
      )
      (libsource (lib "") (part "0805W8F2001T5E"))
    )
    (comp (ref "R75")
      (value "8.2K")
      (fields
        (field (name "BOM_Manufacturer Part") "0805W8F8201T5E")
        (field (name "BOM_Supplier Part") "C17828")
      )
      (libsource (lib "") (part "0805W8F8201T5E"))
    )
    (comp (ref "R76")
      (value "2K")
      (fields
        (field (name "BOM_Manufacturer Part") "0805W8F2001T5E")
        (field (name "BOM_Supplier Part") "C17604")
      )
      (libsource (lib "") (part "0805W8F2001T5E"))
    )
    (comp (ref "R77")
      (value "8.2K")
      (fields
        (field (name "BOM_Manufacturer Part") "0805W8F8201T5E")
        (field (name "BOM_Supplier Part") "C17828")
      )
      (libsource (lib "") (part "0805W8F8201T5E"))
    )
    (comp (ref "VT12") (value "IRLML2803") (libsource (lib "") (part "IRLML2803")))
    (comp (ref "X2")
      (value "32.768KHz")
      (fields
        (field (name "BOM_Manufacturer Part") "EXS00A-MU00202")
        (field (name "BOM_Supplier Part") "C280830")
      )
      (libsource (lib "") (part "EXS00A-MU00202"))
    )
  )
  (nets
    (net (code "1") (name "+3.3V") (class "Default")
      (node (ref "B1") (pin "1") (pinfunction "+_1") (pintype "unspecified"))
      (node (ref "C15") (pin "2") (pinfunction "2_2") (pintype "unspecified"))
      (node (ref "C28") (pin "2") (pinfunction "2_2") (pintype "unspecified"))
      (node (ref "C29") (pin "2") (pinfunction "2_2") (pintype "unspecified"))
      (node (ref "C31") (pin "2") (pinfunction "2_2") (pintype "unspecified"))
      (node (ref "C32") (pin "2") (pinfunction "2_2") (pintype "input"))
      (node (ref "C36") (pin "2") (pinfunction "2_2") (pintype "unspecified"))
      (node (ref "C37") (pin "1") (pinfunction "1_1") (pintype "unspecified"))
      (node (ref "C59") (pin "2") (pinfunction "2_2") (pintype "input"))
      (node (ref "D19") (pin "5") (pinfunction "VCC_5") (pintype "unspecified"))
      (node (ref "DA5") (pin "2") (pinfunction "VOUT_2") (pintype "unspecified"))
      (node (ref "DA5") (pin "4") (pinfunction "VOUT_4") (pintype "unspecified"))
      (node (ref "DD1") (pin "19") (pinfunction "VDD/Power_19") (pintype "unspecified"))
      (node (ref "DD1") (pin "32") (pinfunction "VDD/Power_32") (pintype "unspecified"))
      (node (ref "DD1") (pin "48") (pinfunction "VDD/Power_48") (pintype "unspecified"))
      (node (ref "DD1") (pin "64") (pinfunction "VDD/Power_64") (pintype "unspecified"))
      (node (ref "L1") (pin "1") (pinfunction "1_1") (pintype "unspecified"))
      (node (ref "P18") (pin "1") (pinfunction "1_1") (pintype "input"))
      (node (ref "R33") (pin "1") (pinfunction "1_1") (pintype "unspecified"))
      (node (ref "R58") (pin "1") (pinfunction "1_1") (pintype "input"))
      (node (ref "U4") (pin "8") (pinfunction "VCC2_8") (pintype "unspecified"))
    )
    (net (code "2") (name "AC1") (class "Default")
      (node (ref "P2") (pin "1") (pinfunction "1_1") (pintype "input"))
      (node (ref "P23") (pin "1") (pinfunction "1_1") (pintype "input"))
      (node (ref "P24") (pin "1") (pinfunction "1_1") (pintype "input"))
      (node (ref "P25") (pin "1") (pinfunction "1_1") (pintype "input"))
      (node (ref "P26") (pin "1") (pinfunction "1_1") (pintype "input"))
      (node (ref "P3") (pin "1") (pinfunction "1_1") (pintype "input"))
      (node (ref "VD10") (pin "1") (pinfunction "AC_1") (pintype "unspecified"))
      (node (ref "VD10") (pin "3") (pinfunction "AC_3") (pintype "unspecified"))
      (node (ref "VD11") (pin "2") (pinfunction "C_2") (pintype "unspecified"))
      (node (ref "VT26") (pin "2") (pinfunction "D_2") (pintype "unspecified"))
      (node (ref "VT27") (pin "2") (pinfunction "D_2") (pintype "unspecified"))
      (node (ref "VT28") (pin "2") (pinfunction "D_2") (pintype "unspecified"))
      (node (ref "VT29") (pin "2") (pinfunction "D_2") (pintype "unspecified"))
    )
    (net (code "3") (name "AC2") (class "Default")
      (node (ref "P27") (pin "1") (pinfunction "1_1") (pintype "input"))
      (node (ref "P28") (pin "1") (pinfunction "1_1") (pintype "input"))
      (node (ref "P29") (pin "1") (pinfunction "1_1") (pintype "input"))
      (node (ref "P30") (pin "1") (pinfunction "1_1") (pintype "input"))
      (node (ref "P31") (pin "1") (pinfunction "1_1") (pintype "input"))
      (node (ref "P60") (pin "1") (pinfunction "1_1") (pintype "input"))
      (node (ref "VD12") (pin "2") (pinfunction "C_2") (pintype "unspecified"))
      (node (ref "VD13") (pin "1") (pinfunction "AC_1") (pintype "unspecified"))
      (node (ref "VD13") (pin "3") (pinfunction "AC_3") (pintype "unspecified"))
      (node (ref "VT24") (pin "2") (pinfunction "D_2") (pintype "unspecified"))
      (node (ref "VT25") (pin "2") (pinfunction "D_2") (pintype "unspecified"))
      (node (ref "VT30") (pin "2") (pinfunction "D_2") (pintype "unspecified"))
      (node (ref "VT31") (pin "2") (pinfunction "D_2") (pintype "unspecified"))
    )
    (net (code "4") (name "ADC1_In8") (class "Default")
      (node (ref "DD1") (pin "8") (pinfunction "PC0/I/O/GPIO_EXTI0_8") (pintype "unspecified"))
      (node (ref "R11") (pin "1") (pinfunction "1_1") (pintype "input"))
      (node (ref "R35") (pin "2") (pinfunction "2_2") (pintype "input"))
    )
    (net (code "5") (name "ADC1_In9") (class "Default")
      (node (ref "DD1") (pin "9") (pinfunction "PC1/I/O/GPIO_EXTI1_9") (pintype "unspecified"))
      (node (ref "R16") (pin "1") (pinfunction "1_1") (pintype "input"))
      (node (ref "R37") (pin "2") (pinfunction "2_2") (pintype "input"))
    )
    (net (code "6") (name "ADC1_In11") (class "Default")
      (node (ref "DD1") (pin "26") (pinfunction "PB0/I/O/COMP4_INPOPAMP2_VINP/_26") (pintype "unspecified"))
      (node (ref "R28") (pin "1") (pinfunction "1_1") (pintype "input"))
      (node (ref "R29") (pin "2") (pinfunction "2_2") (pintype "input"))
    )
    (net (code "7") (name "ADC1_In12") (class "Default")
      (node (ref "DD1") (pin "27") (pinfunction "PB1/I/O_27") (pintype "unspecified"))
      (node (ref "R74") (pin "2") (pinfunction "2_2") (pintype "input"))
      (node (ref "R75") (pin "1") (pinfunction "1_1") (pintype "input"))
    )
    (net (code "8") (name "ADC2_In10") (class "Default")
      (node (ref "DD1") (pin "10") (pinfunction "PC2/I/O/GPIO_EXTI2_10") (pintype "unspecified"))
      (node (ref "R17") (pin "1") (pinfunction "1_1") (pintype "input"))
      (node (ref "R38") (pin "2") (pinfunction "2_2") (pintype "input"))
    )
    (net (code "9") (name "ADC2_In11") (class "Default")
      (node (ref "DD1") (pin "11") (pinfunction "PC3/I/O/GPIO_EXTI3_11") (pintype "unspecified"))
      (node (ref "R18") (pin "1") (pinfunction "1_1") (pintype "input"))
      (node (ref "R39") (pin "2") (pinfunction "2_2") (pintype "input"))
    )
    (net (code "10") (name "ADC2_In12") (class "Default")
      (node (ref "DD1") (pin "28") (pinfunction "PB2/I/O_28") (pintype "unspecified"))
      (node (ref "R76") (pin "2") (pinfunction "2_2") (pintype "input"))
      (node (ref "R77") (pin "1") (pinfunction "1_1") (pintype "input"))
    )
    (net (code "11") (name "ALARM_BUZZ") (class "Default")
      (node (ref "DD1") (pin "2") (pinfunction "PC13/Output/GPIO_Output_2") (pintype "unspecified"))
      (node (ref "R6") (pin "2") (pinfunction "2_2") (pintype "unspecified"))
      (node (ref "VT12") (pin "1") (pinfunction "G_1") (pintype "unspecified"))
    )
    (net (code "12") (name "AVDD") (class "Default")
      (node (ref "C41") (pin "1") (pinfunction "1_1") (pintype "input"))
      (node (ref "C61") (pin "2") (pinfunction "2_2") (pintype "unspecified"))
      (node (ref "DD1") (pin "13") (pinfunction "VDDA/VREFp/Power_13") (pintype "unspecified"))
      (node (ref "L1") (pin "2") (pinfunction "2_2") (pintype "unspecified"))
    )
    (net (code "13") (name "Akk1") (class "Default")
      (node (ref "P33") (pin "1") (pinfunction "1_1") (pintype "input"))
      (node (ref "P34") (pin "1") (pinfunction "1_1") (pintype "input"))
      (node (ref "P35") (pin "1") (pinfunction "1_1") (pintype "input"))
      (node (ref "P36") (pin "1") (pinfunction "1_1") (pintype "input"))
      (node (ref "P40") (pin "1") (pinfunction "1_1") (pintype "input"))
      (node (ref "P41") (pin "1") (pinfunction "1_1") (pintype "input"))
      (node (ref "R11") (pin "2") (pinfunction "2_2") (pintype "input"))
      (node (ref "VD7") (pin "1") (pinfunction "A_1") (pintype "unspecified"))
      (node (ref "VT10") (pin "2") (pinfunction "D_2") (pintype "unspecified"))
      (node (ref "VT11") (pin "2") (pinfunction "D_2") (pintype "unspecified"))
      (node (ref "VT13") (pin "2") (pinfunction "D_2") (pintype "unspecified"))
      (node (ref "VT18") (pin "2") (pinfunction "D_2") (pintype "unspecified"))
      (node (ref "VT22") (pin "2") (pinfunction "D_2") (pintype "unspecified"))
      (node (ref "VT9") (pin "2") (pinfunction "D_2") (pintype "unspecified"))
    )
    (net (code "14") (name "Akk2") (class "Default")
      (node (ref "P16") (pin "1") (pinfunction "1_1") (pintype "input"))
      (node (ref "P17") (pin "1") (pinfunction "1_1") (pintype "input"))
      (node (ref "P32") (pin "1") (pinfunction "1_1") (pintype "input"))
      (node (ref "P37") (pin "1") (pinfunction "1_1") (pintype "input"))
      (node (ref "P38") (pin "1") (pinfunction "1_1") (pintype "input"))
      (node (ref "P39") (pin "1") (pinfunction "1_1") (pintype "input"))
      (node (ref "R16") (pin "2") (pinfunction "2_2") (pintype "input"))
      (node (ref "VD8") (pin "1") (pinfunction "A_1") (pintype "unspecified"))
      (node (ref "VT16") (pin "2") (pinfunction "D_2") (pintype "unspecified"))
      (node (ref "VT17") (pin "2") (pinfunction "D_2") (pintype "unspecified"))
      (node (ref "VT19") (pin "2") (pinfunction "D_2") (pintype "unspecified"))
      (node (ref "VT23") (pin "2") (pinfunction "D_2") (pintype "unspecified"))
      (node (ref "VT5") (pin "2") (pinfunction "D_2") (pintype "unspecified"))
      (node (ref "VT6") (pin "2") (pinfunction "D_2") (pintype "unspecified"))
    )
    (net (code "15") (name "BOOT0") (class "Default")
      (node (ref "DD1") (pin "60") (pinfunction "BOOT0/Boot_60") (pintype "unspecified"))
      (node (ref "R34") (pin "1") (pinfunction "1_1") (pintype "unspecified"))
    )
    (net (code "16") (name "Boost1") (class "Default")
      (node (ref "C3") (pin "2") (pinfunction "2_2") (pintype "input"))
      (node (ref "C4") (pin "2") (pinfunction "2_2") (pintype "input"))
      (node (ref "D1") (pin "8") (pinfunction "VB_8") (pintype "unspecified"))
      (node (ref "D5") (pin "6") (pinfunction "BOOST_6") (pintype "unspecified"))
      (node (ref "VD1") (pin "2") (pinfunction "K_2") (pintype "unspecified"))
    )
    (net (code "17") (name "Boost2") (class "Default")
      (node (ref "C7") (pin "2") (pinfunction "2_2") (pintype "input"))
      (node (ref "C8") (pin "2") (pinfunction "2_2") (pintype "input"))
      (node (ref "D2") (pin "8") (pinfunction "VB_8") (pintype "unspecified"))
      (node (ref "D6") (pin "6") (pinfunction "BOOST_6") (pintype "unspecified"))
      (node (ref "VD2") (pin "2") (pinfunction "K_2") (pintype "unspecified"))
    )
    (net (code "18") (name "Boost3") (class "Default")
      (node (ref "C18") (pin "2") (pinfunction "2_2") (pintype "input"))
      (node (ref "C19") (pin "2") (pinfunction "2_2") (pintype "input"))
      (node (ref "D10") (pin "8") (pinfunction "VB_8") (pintype "unspecified"))
      (node (ref "D11") (pin "6") (pinfunction "BOOST_6") (pintype "unspecified"))
      (node (ref "VD4") (pin "2") (pinfunction "K_2") (pintype "unspecified"))
    )
    (net (code "19") (name "Boost4") (class "Default")
      (node (ref "C12") (pin "2") (pinfunction "2_2") (pintype "input"))
      (node (ref "C9") (pin "2") (pinfunction "2_2") (pintype "input"))
      (node (ref "D7") (pin "6") (pinfunction "BOOST_6") (pintype "unspecified"))
      (node (ref "D9") (pin "8") (pinfunction "VB_8") (pintype "unspecified"))
      (node (ref "VD3") (pin "2") (pinfunction "K_2") (pintype "unspecified"))
    )
    (net (code "20") (name "Boost5") (class "Default")
      (node (ref "C24") (pin "2") (pinfunction "2_2") (pintype "input"))
      (node (ref "C25") (pin "2") (pinfunction "2_2") (pintype "input"))
      (node (ref "D12") (pin "8") (pinfunction "VB_8") (pintype "unspecified"))
      (node (ref "D8") (pin "6") (pinfunction "BOOST_6") (pintype "unspecified"))
      (node (ref "VD5") (pin "2") (pinfunction "K_2") (pintype "unspecified"))
    )
    (net (code "21") (name "Boost6") (class "Default")
      (node (ref "C26") (pin "2") (pinfunction "2_2") (pintype "input"))
      (node (ref "C62") (pin "2") (pinfunction "2_2") (pintype "input"))
      (node (ref "D13") (pin "8") (pinfunction "VB_8") (pintype "unspecified"))
      (node (ref "D14") (pin "6") (pinfunction "BOOST_6") (pintype "unspecified"))
      (node (ref "VD6") (pin "2") (pinfunction "K_2") (pintype "unspecified"))
    )
    (net (code "22") (name "Ch_Akk1") (class "Default")
      (node (ref "R30") (pin "1") (pinfunction "1_1") (pintype "input"))
      (node (ref "R67") (pin "1") (pinfunction "1_1") (pintype "input"))
      (node (ref "VT20") (pin "1") (pinfunction "G_1") (pintype "unspecified"))
    )
    (net (code "23") (name "Ch_Akk2") (class "Default")
      (node (ref "R62") (pin "1") (pinfunction "1_1") (pintype "input"))
      (node (ref "R68") (pin "1") (pinfunction "1_1") (pintype "input"))
      (node (ref "VT21") (pin "1") (pinfunction "G_1") (pintype "unspecified"))
    )
    (net (code "24") (name "Coil1") (class "Default")
      (node (ref "C18") (pin "1") (pinfunction "1_1") (pintype "input"))
      (node (ref "C19") (pin "1") (pinfunction "1_1") (pintype "input"))
      (node (ref "C24") (pin "1") (pinfunction "1_1") (pintype "input"))
      (node (ref "C25") (pin "1") (pinfunction "1_1") (pintype "input"))
      (node (ref "C3") (pin "1") (pinfunction "1_1") (pintype "input"))
      (node (ref "C4") (pin "1") (pinfunction "1_1") (pintype "input"))
      (node (ref "D1") (pin "6") (pinfunction "VS_6") (pintype "unspecified"))
      (node (ref "D10") (pin "6") (pinfunction "VS_6") (pintype "unspecified"))
      (node (ref "D11") (pin "8") (pinfunction "TS_8") (pintype "unspecified"))
      (node (ref "D12") (pin "6") (pinfunction "VS_6") (pintype "unspecified"))
      (node (ref "D5") (pin "8") (pinfunction "TS_8") (pintype "unspecified"))
      (node (ref "D8") (pin "8") (pinfunction "TS_8") (pintype "unspecified"))
      (node (ref "P10") (pin "1") (pinfunction "1_1") (pintype "input"))
      (node (ref "P11") (pin "1") (pinfunction "1_1") (pintype "input"))
      (node (ref "P12") (pin "1") (pinfunction "1_1") (pintype "input"))
      (node (ref "P4") (pin "1") (pinfunction "1_1") (pintype "input"))
      (node (ref "P5") (pin "1") (pinfunction "1_1") (pintype "input"))
      (node (ref "P6") (pin "1") (pinfunction "1_1") (pintype "input"))
      (node (ref "R20") (pin "1") (pinfunction "1_1") (pintype "input"))
      (node (ref "R21") (pin "1") (pinfunction "1_1") (pintype "input"))
      (node (ref "R22") (pin "1") (pinfunction "1_1") (pintype "input"))
      (node (ref "VT1") (pin "2") (pinfunction "D_2") (pintype "unspecified"))
      (node (ref "VT10") (pin "3") (pinfunction "S_3") (pintype "unspecified"))
      (node (ref "VT2") (pin "2") (pinfunction "D_2") (pintype "unspecified"))
      (node (ref "VT5") (pin "3") (pinfunction "S_3") (pintype "unspecified"))
      (node (ref "VT6") (pin "3") (pinfunction "S_3") (pintype "unspecified"))
      (node (ref "VT7") (pin "3") (pinfunction "S_3") (pintype "unspecified"))
      (node (ref "VT8") (pin "3") (pinfunction "S_3") (pintype "unspecified"))
      (node (ref "VT9") (pin "3") (pinfunction "S_3") (pintype "unspecified"))
    )
    (net (code "25") (name "Coil2") (class "Default")
      (node (ref "C12") (pin "1") (pinfunction "1_1") (pintype "input"))
      (node (ref "C26") (pin "1") (pinfunction "1_1") (pintype "input"))
      (node (ref "C62") (pin "1") (pinfunction "1_1") (pintype "input"))
      (node (ref "C7") (pin "1") (pinfunction "1_1") (pintype "input"))
      (node (ref "C8") (pin "1") (pinfunction "1_1") (pintype "input"))
      (node (ref "C9") (pin "1") (pinfunction "1_1") (pintype "input"))
      (node (ref "D13") (pin "6") (pinfunction "VS_6") (pintype "unspecified"))
      (node (ref "D14") (pin "8") (pinfunction "TS_8") (pintype "unspecified"))
      (node (ref "D2") (pin "6") (pinfunction "VS_6") (pintype "unspecified"))
      (node (ref "D6") (pin "8") (pinfunction "TS_8") (pintype "unspecified"))
      (node (ref "D7") (pin "8") (pinfunction "TS_8") (pintype "unspecified"))
      (node (ref "D9") (pin "6") (pinfunction "VS_6") (pintype "unspecified"))
      (node (ref "P13") (pin "1") (pinfunction "1_1") (pintype "input"))
      (node (ref "P14") (pin "1") (pinfunction "1_1") (pintype "input"))
      (node (ref "P15") (pin "1") (pinfunction "1_1") (pintype "input"))
      (node (ref "P7") (pin "1") (pinfunction "1_1") (pintype "input"))
      (node (ref "P8") (pin "1") (pinfunction "1_1") (pintype "input"))
      (node (ref "P9") (pin "1") (pinfunction "1_1") (pintype "input"))
      (node (ref "R23") (pin "2") (pinfunction "2_2") (pintype "input"))
      (node (ref "R24") (pin "1") (pinfunction "1_1") (pintype "input"))
      (node (ref "R25") (pin "2") (pinfunction "2_2") (pintype "input"))
      (node (ref "VT11") (pin "3") (pinfunction "S_3") (pintype "unspecified"))
      (node (ref "VT13") (pin "3") (pinfunction "S_3") (pintype "unspecified"))
      (node (ref "VT14") (pin "3") (pinfunction "S_3") (pintype "unspecified"))
      (node (ref "VT15") (pin "3") (pinfunction "S_3") (pintype "unspecified"))
      (node (ref "VT16") (pin "3") (pinfunction "S_3") (pintype "unspecified"))
      (node (ref "VT17") (pin "3") (pinfunction "S_3") (pintype "unspecified"))
      (node (ref "VT3") (pin "2") (pinfunction "D_2") (pintype "unspecified"))
      (node (ref "VT4") (pin "2") (pinfunction "D_2") (pintype "unspecified"))
    )
    (net (code "26") (name "DisCh_Akk1") (class "Default")
      (node (ref "R7") (pin "1") (pinfunction "1_1") (pintype "input"))
      (node (ref "R71") (pin "1") (pinfunction "1_1") (pintype "input"))
      (node (ref "VT22") (pin "1") (pinfunction "G_1") (pintype "unspecified"))
    )
    (net (code "27") (name "DisCh_Akk2") (class "Default")
      (node (ref "R59") (pin "1") (pinfunction "1_1") (pintype "input"))
      (node (ref "R72") (pin "1") (pinfunction "1_1") (pintype "input"))
      (node (ref "VT23") (pin "1") (pinfunction "G_1") (pintype "unspecified"))
    )
    (net (code "28") (name "GND") (class "Default")
      (node (ref "C1") (pin "1") (pinfunction "1_1") (pintype "input"))
      (node (ref "C10") (pin "1") (pinfunction "1_1") (pintype "input"))
      (node (ref "C11") (pin "1") (pinfunction "1_1") (pintype "input"))
      (node (ref "C13") (pin "1") (pinfunction "1_1") (pintype "input"))
      (node (ref "C15") (pin "1") (pinfunction "1_1") (pintype "unspecified"))
      (node (ref "C2") (pin "1") (pinfunction "1_1") (pintype "input"))
      (node (ref "C20") (pin "1") (pinfunction "1_1") (pintype "input"))
      (node (ref "C21") (pin "1") (pinfunction "1_1") (pintype "input"))
      (node (ref "C22") (pin "1") (pinfunction "1_1") (pintype "input"))
      (node (ref "C23") (pin "1") (pinfunction "1_1") (pintype "input"))
      (node (ref "C27") (pin "1") (pinfunction "1_1") (pintype "input"))
      (node (ref "C28") (pin "1") (pinfunction "1_1") (pintype "unspecified"))
      (node (ref "C29") (pin "1") (pinfunction "1_1") (pintype "unspecified"))
      (node (ref "C30") (pin "2") (pinfunction "2_2") (pintype "input"))
      (node (ref "C31") (pin "1") (pinfunction "1_1") (pintype "unspecified"))
      (node (ref "C32") (pin "1") (pinfunction "1_1") (pintype "input"))
      (node (ref "C35") (pin "1") (pinfunction "1_1") (pintype "unspecified"))
      (node (ref "C36") (pin "1") (pinfunction "1_1") (pintype "unspecified"))
      (node (ref "C37") (pin "2") (pinfunction "2_2") (pintype "unspecified"))
      (node (ref "C38") (pin "1") (pinfunction "1_1") (pintype "input"))
      (node (ref "C39") (pin "2") (pinfunction "2_2") (pintype "input"))
      (node (ref "C40") (pin "2") (pinfunction "2_2") (pintype "input"))
      (node (ref "C41") (pin "2") (pinfunction "2_2") (pintype "input"))
      (node (ref "C5") (pin "1") (pinfunction "1_1") (pintype "input"))
      (node (ref "C50") (pin "2") (pinfunction "2_2") (pintype "input"))
      (node (ref "C51") (pin "2") (pinfunction "2_2") (pintype "input"))
      (node (ref "C52") (pin "2") (pinfunction "2_2") (pintype "input"))
      (node (ref "C57") (pin "1") (pinfunction "1_1") (pintype "input"))
      (node (ref "C58") (pin "2") (pinfunction "2_2") (pintype "input"))
      (node (ref "C59") (pin "1") (pinfunction "1_1") (pintype "input"))
      (node (ref "C6") (pin "1") (pinfunction "1_1") (pintype "input"))
      (node (ref "C61") (pin "1") (pinfunction "1_1") (pintype "unspecified"))
      (node (ref "C63") (pin "1") (pinfunction "1_1") (pintype "input"))
      (node (ref "C64") (pin "1") (pinfunction "1_1") (pintype "input"))
      (node (ref "C65") (pin "1") (pinfunction "1_1") (pintype "input"))
      (node (ref "C66") (pin "2") (pinfunction "2_2") (pintype "input"))
      (node (ref "C67") (pin "2") (pinfunction "2_2") (pintype "input"))
      (node (ref "D1") (pin "3") (pinfunction "COM_3") (pintype "unspecified"))
      (node (ref "D10") (pin "3") (pinfunction "COM_3") (pintype "unspecified"))
      (node (ref "D11") (pin "2") (pinfunction "GND_2") (pintype "passive"))
      (node (ref "D11") (pin "4") (pinfunction "GND_4") (pintype "passive"))
      (node (ref "D11") (pin "9") (pinfunction "EP_9") (pintype "passive"))
      (node (ref "D12") (pin "3") (pinfunction "COM_3") (pintype "unspecified"))
      (node (ref "D13") (pin "3") (pinfunction "COM_3") (pintype "unspecified"))
      (node (ref "D14") (pin "2") (pinfunction "GND_2") (pintype "passive"))
      (node (ref "D14") (pin "4") (pinfunction "GND_4") (pintype "passive"))
      (node (ref "D14") (pin "9") (pinfunction "EP_9") (pintype "passive"))
      (node (ref "D15") (pin "2") (pinfunction "GND_2") (pintype "unspecified"))
      (node (ref "D16") (pin "2") (pinfunction "GND_2") (pintype "unspecified"))
      (node (ref "D17") (pin "2") (pinfunction "GND_2") (pintype "unspecified"))
      (node (ref "D18") (pin "2") (pinfunction "GND_2") (pintype "unspecified"))
      (node (ref "D19") (pin "2") (pinfunction "GND_2") (pintype "unspecified"))
      (node (ref "D2") (pin "3") (pinfunction "COM_3") (pintype "unspecified"))
      (node (ref "D3") (pin "4") (pinfunction "GND_4") (pintype "unspecified"))
      (node (ref "D3") (pin "5") (pinfunction "GND_5") (pintype "unspecified"))
      (node (ref "D3") (pin "9") (pinfunction "EXP_9") (pintype "unspecified"))
      (node (ref "D4") (pin "4") (pinfunction "GND_4") (pintype "unspecified"))
      (node (ref "D4") (pin "5") (pinfunction "GND_5") (pintype "unspecified"))
      (node (ref "D4") (pin "9") (pinfunction "EXP_9") (pintype "unspecified"))
      (node (ref "D5") (pin "2") (pinfunction "GND_2") (pintype "passive"))
      (node (ref "D5") (pin "4") (pinfunction "GND_4") (pintype "passive"))
      (node (ref "D5") (pin "9") (pinfunction "EP_9") (pintype "passive"))
      (node (ref "D6") (pin "2") (pinfunction "GND_2") (pintype "passive"))
      (node (ref "D6") (pin "4") (pinfunction "GND_4") (pintype "passive"))
      (node (ref "D6") (pin "9") (pinfunction "EP_9") (pintype "passive"))
      (node (ref "D7") (pin "2") (pinfunction "GND_2") (pintype "passive"))
      (node (ref "D7") (pin "4") (pinfunction "GND_4") (pintype "passive"))
      (node (ref "D7") (pin "9") (pinfunction "EP_9") (pintype "passive"))
      (node (ref "D8") (pin "2") (pinfunction "GND_2") (pintype "passive"))
      (node (ref "D8") (pin "4") (pinfunction "GND_4") (pintype "passive"))
      (node (ref "D8") (pin "9") (pinfunction "EP_9") (pintype "passive"))
      (node (ref "D9") (pin "3") (pinfunction "COM_3") (pintype "unspecified"))
      (node (ref "DA5") (pin "1") (pinfunction "GND_1") (pintype "unspecified"))
      (node (ref "DD1") (pin "12") (pinfunction "VSSA/VREFm/Power_12") (pintype "unspecified"))
      (node (ref "DD1") (pin "18") (pinfunction "VSS/Power_18") (pintype "unspecified"))
      (node (ref "DD1") (pin "31") (pinfunction "VSS/Power_31") (pintype "unspecified"))
      (node (ref "DD1") (pin "47") (pinfunction "VSS/Power_47") (pintype "unspecified"))
      (node (ref "DD1") (pin "63") (pinfunction "VSS/Power_63") (pintype "unspecified"))
      (node (ref "H1") (pin "2") (pinfunction "2_2") (pintype "input"))
      (node (ref "H3") (pin "2") (pinfunction "2_2") (pintype "input"))
      (node (ref "L2") (pin "2") (pinfunction "2_2") (pintype "unspecified"))
      (node (ref "P1") (pin "2") (pinfunction "2_2") (pintype "unspecified"))
      (node (ref "P19") (pin "1") (pinfunction "1_1") (pintype "input"))
      (node (ref "P22") (pin "1") (pinfunction "1_1") (pintype "input"))
      (node (ref "R29") (pin "1") (pinfunction "1_1") (pintype "input"))
      (node (ref "R34") (pin "2") (pinfunction "2_2") (pintype "unspecified"))
      (node (ref "R35") (pin "1") (pinfunction "1_1") (pintype "input"))
      (node (ref "R37") (pin "1") (pinfunction "1_1") (pintype "input"))
      (node (ref "R38") (pin "1") (pinfunction "1_1") (pintype "input"))
      (node (ref "R39") (pin "1") (pinfunction "1_1") (pintype "input"))
      (node (ref "R54") (pin "1") (pinfunction "1_1") (pintype "input"))
      (node (ref "R55") (pin "1") (pinfunction "1_1") (pintype "input"))
      (node (ref "R6") (pin "1") (pinfunction "1_1") (pintype "unspecified"))
      (node (ref "R60") (pin "1") (pinfunction "1_1") (pintype "input"))
      (node (ref "R61") (pin "1") (pinfunction "1_1") (pintype "input"))
      (node (ref "R65") (pin "1") (pinfunction "1_1") (pintype "input"))
      (node (ref "R67") (pin "2") (pinfunction "2_2") (pintype "input"))
      (node (ref "R68") (pin "2") (pinfunction "2_2") (pintype "input"))
      (node (ref "R74") (pin "1") (pinfunction "1_1") (pintype "input"))
      (node (ref "R76") (pin "1") (pinfunction "1_1") (pintype "input"))
      (node (ref "U4") (pin "5") (pinfunction "GND2_5") (pintype "unspecified"))
      (node (ref "VT12") (pin "2") (pinfunction "S_2") (pintype "unspecified"))
      (node (ref "VT20") (pin "2") (pinfunction "S_2") (pintype "unspecified"))
      (node (ref "VT21") (pin "2") (pinfunction "S_2") (pintype "unspecified"))
    )
    (net (code "29") (name "Gen") (class "Default")
      (node (ref "P42") (pin "1") (pinfunction "1_1") (pintype "input"))
      (node (ref "P43") (pin "1") (pinfunction "1_1") (pintype "input"))
      (node (ref "P44") (pin "1") (pinfunction "1_1") (pintype "input"))
      (node (ref "P45") (pin "1") (pinfunction "1_1") (pintype "input"))
      (node (ref "P46") (pin "1") (pinfunction "1_1") (pintype "input"))
      (node (ref "P47") (pin "1") (pinfunction "1_1") (pintype "input"))
      (node (ref "R17") (pin "2") (pinfunction "2_2") (pintype "input"))
      (node (ref "R63") (pin "1") (pinfunction "1_1") (pintype "input"))
      (node (ref "R64") (pin "2") (pinfunction "2_2") (pintype "input"))
      (node (ref "VD9") (pin "1") (pinfunction "A_1") (pintype "unspecified"))
      (node (ref "VT14") (pin "2") (pinfunction "D_2") (pintype "unspecified"))
      (node (ref "VT15") (pin "2") (pinfunction "D_2") (pintype "unspecified"))
      (node (ref "VT18") (pin "3") (pinfunction "S_3") (pintype "unspecified"))
      (node (ref "VT19") (pin "3") (pinfunction "S_3") (pintype "unspecified"))
      (node (ref "VT7") (pin "2") (pinfunction "D_2") (pintype "unspecified"))
      (node (ref "VT8") (pin "2") (pinfunction "D_2") (pintype "unspecified"))
    )
    (net (code "30") (name "Hrtim_ChA1") (class "Default")
      (node (ref "DD1") (pin "44") (pinfunction "PA11/Output/GPIO_Output_44") (pintype "unspecified"))
      (node (ref "R31") (pin "1") (pinfunction "1_1") (pintype "input"))
    )
    (net (code "31") (name "Hrtim_ChA2") (class "Default")
      (node (ref "DD1") (pin "43") (pinfunction "PA10/Output/GPIO_Output_43") (pintype "unspecified"))
      (node (ref "R3") (pin "1") (pinfunction "1_1") (pintype "input"))
    )
    (net (code "32") (name "Hrtim_ChB1") (class "Default")
      (node (ref "DD1") (pin "42") (pinfunction "PA9/Output/GPIO_Output_42") (pintype "unspecified"))
      (node (ref "R4") (pin "1") (pinfunction "1_1") (pintype "input"))
    )
    (net (code "33") (name "Hrtim_ChB2") (class "Default")
      (node (ref "DD1") (pin "41") (pinfunction "PA8/Output/GPIO_Output_41") (pintype "unspecified"))
      (node (ref "R5") (pin "1") (pinfunction "1_1") (pintype "input"))
    )
    (net (code "34") (name "Hrtim_ChC1") (class "Default")
      (node (ref "DD1") (pin "33") (pinfunction "PB12/I/O_33") (pintype "unspecified"))
      (node (ref "R12") (pin "2") (pinfunction "2_2") (pintype "input"))
    )
    (net (code "35") (name "Hrtim_ChC2") (class "Default")
      (node (ref "DD1") (pin "34") (pinfunction "PB13/I/O/ADC1_IN13_34") (pintype "unspecified"))
      (node (ref "R13") (pin "2") (pinfunction "2_2") (pintype "input"))
    )
    (net (code "36") (name "Hrtim_ChD1") (class "Default")
      (node (ref "DD1") (pin "35") (pinfunction "PB14/Output/GPIO_Output_35") (pintype "unspecified"))
      (node (ref "R14") (pin "2") (pinfunction "2_2") (pintype "input"))
    )
    (net (code "37") (name "Hrtim_ChD2") (class "Default")
      (node (ref "DD1") (pin "36") (pinfunction "PB15/Output/GPIO_Output_36") (pintype "unspecified"))
      (node (ref "R15") (pin "2") (pinfunction "2_2") (pintype "input"))
    )
    (net (code "38") (name "Hrtim_ChE1") (class "Default")
      (node (ref "DD1") (pin "39") (pinfunction "PC8/Output/GPIO_Output_39") (pintype "unspecified"))
      (node (ref "R9") (pin "1") (pinfunction "1_1") (pintype "input"))
    )
    (net (code "39") (name "Hrtim_ChE2") (class "Default")
      (node (ref "DD1") (pin "40") (pinfunction "PC9/Output/GPIO_Output_40") (pintype "unspecified"))
      (node (ref "R10") (pin "1") (pinfunction "1_1") (pintype "input"))
    )
    (net (code "40") (name "Left_Dwn") (class "Default")
      (node (ref "D1") (pin "4") (pinfunction "LO_4") (pintype "unspecified"))
      (node (ref "D3") (pin "6") (pinfunction "OUT_6") (pintype "unspecified"))
      (node (ref "D3") (pin "7") (pinfunction "OUT_7") (pintype "unspecified"))
      (node (ref "R26") (pin "1") (pinfunction "1_1") (pintype "input"))
    )
    (net (code "41") (name "Left_Dwn_In") (class "Default")
      (node (ref "D1") (pin "2") (pinfunction "LIN_2") (pintype "unspecified"))
      (node (ref "D3") (pin "2") (pinfunction "IN_2") (pintype "unspecified"))
      (node (ref "R3") (pin "2") (pinfunction "2_2") (pintype "input"))
    )
    (net (code "42") (name "Left_Rec") (class "Default")
      (node (ref "D18") (pin "3") (pinfunction "IN+_3") (pintype "unspecified"))
      (node (ref "D19") (pin "3") (pinfunction "2A_3") (pintype "unspecified"))
      (node (ref "R58") (pin "2") (pinfunction "2_2") (pintype "input"))
      (node (ref "R9") (pin "2") (pinfunction "2_2") (pintype "input"))
    )
    (net (code "43") (name "Left_Up1") (class "Default")
      (node (ref "D1") (pin "7") (pinfunction "HO_7") (pintype "unspecified"))
      (node (ref "D5") (pin "7") (pinfunction "TG_7") (pintype "output"))
      (node (ref "R27") (pin "1") (pinfunction "1_1") (pintype "input"))
    )
    (net (code "44") (name "Left_Up1_In") (class "Default")
      (node (ref "D1") (pin "1") (pinfunction "HIN_1") (pintype "unspecified"))
      (node (ref "D5") (pin "1") (pinfunction "INP_1") (pintype "unspecified"))
      (node (ref "R5") (pin "2") (pinfunction "2_2") (pintype "input"))
    )
    (net (code "45") (name "Left_Up2") (class "Default")
      (node (ref "D10") (pin "7") (pinfunction "HO_7") (pintype "unspecified"))
      (node (ref "D11") (pin "7") (pinfunction "TG_7") (pintype "output"))
      (node (ref "R51") (pin "1") (pinfunction "1_1") (pintype "input"))
    )
    (net (code "46") (name "Left_Up2_In") (class "Default")
      (node (ref "D10") (pin "1") (pinfunction "HIN_1") (pintype "unspecified"))
      (node (ref "D11") (pin "1") (pinfunction "INP_1") (pintype "unspecified"))
      (node (ref "R12") (pin "1") (pinfunction "1_1") (pintype "input"))
    )
    (net (code "47") (name "Left_Up3") (class "Default")
      (node (ref "D12") (pin "7") (pinfunction "HO_7") (pintype "unspecified"))
      (node (ref "D8") (pin "7") (pinfunction "TG_7") (pintype "output"))
      (node (ref "R52") (pin "1") (pinfunction "1_1") (pintype "input"))
    )
    (net (code "48") (name "Left_Up3_In") (class "Default")
      (node (ref "D12") (pin "1") (pinfunction "HIN_1") (pintype "unspecified"))
      (node (ref "D8") (pin "1") (pinfunction "INP_1") (pintype "unspecified"))
      (node (ref "R14") (pin "1") (pinfunction "1_1") (pintype "input"))
    )
    (net (code "49") (name "NRST") (class "Default")
      (node (ref "C30") (pin "1") (pinfunction "1_1") (pintype "input"))
      (node (ref "DD1") (pin "7") (pinfunction "NRST/Reset_7") (pintype "unspecified"))
      (node (ref "H1") (pin "1") (pinfunction "1_1") (pintype "input"))
      (node (ref "R33") (pin "2") (pinfunction "2_2") (pintype "unspecified"))
    )
    (net (code "50") (name "Net-(D9-LIN)") (class "Default")
      (node (ref "D9") (pin "2") (pinfunction "LIN_2") (pintype "unspecified"))
      (node (ref "R54") (pin "2") (pinfunction "2_2") (pintype "input"))
    )
    (net (code "51") (name "Net-(D10-LIN)") (class "Default")
      (node (ref "D10") (pin "2") (pinfunction "LIN_2") (pintype "unspecified"))
      (node (ref "R55") (pin "2") (pinfunction "2_2") (pintype "input"))
    )
    (net (code "52") (name "Net-(D12-LIN)") (class "Default")
      (node (ref "D12") (pin "2") (pinfunction "LIN_2") (pintype "unspecified"))
      (node (ref "R60") (pin "2") (pinfunction "2_2") (pintype "input"))
    )
    (net (code "53") (name "Net-(D13-LIN)") (class "Default")
      (node (ref "D13") (pin "2") (pinfunction "LIN_2") (pintype "unspecified"))
      (node (ref "R61") (pin "2") (pinfunction "2_2") (pintype "input"))
    )
    (net (code "54") (name "Net-(D15-IN+)") (class "Default")
      (node (ref "D15") (pin "3") (pinfunction "IN+_3") (pintype "unspecified"))
      (node (ref "R73") (pin "1") (pinfunction "1_1") (pintype "input"))
    )
    (net (code "55") (name "Net-(D15-OUT)") (class "Default")
      (node (ref "D15") (pin "4") (pinfunction "OUT_4") (pintype "unspecified"))
      (node (ref "R53") (pin "2") (pinfunction "2_2") (pintype "input"))
    )
    (net (code "56") (name "Net-(D16-IN+)") (class "Default")
      (node (ref "D16") (pin "3") (pinfunction "IN+_3") (pintype "unspecified"))
      (node (ref "R66") (pin "1") (pinfunction "1_1") (pintype "input"))
    )
    (net (code "57") (name "Net-(D16-OUT)") (class "Default")
      (node (ref "D16") (pin "4") (pinfunction "OUT_4") (pintype "unspecified"))
      (node (ref "R42") (pin "2") (pinfunction "2_2") (pintype "input"))
    )
    (net (code "58") (name "Net-(D17-OUT)") (class "Default")
      (node (ref "D17") (pin "4") (pinfunction "OUT_4") (pintype "unspecified"))
      (node (ref "R40") (pin "2") (pinfunction "2_2") (pintype "input"))
    )
    (net (code "59") (name "Net-(D18-OUT)") (class "Default")
      (node (ref "D18") (pin "4") (pinfunction "OUT_4") (pintype "unspecified"))
      (node (ref "R57") (pin "2") (pinfunction "2_2") (pintype "input"))
    )
    (net (code "60") (name "Net-(D19-1Y)") (class "Default")
      (node (ref "D19") (pin "6") (pinfunction "1Y_6") (pintype "unspecified"))
      (node (ref "R73") (pin "2") (pinfunction "2_2") (pintype "input"))
    )
    (net (code "61") (name "Net-(D19-2Y)") (class "Default")
      (node (ref "D19") (pin "4") (pinfunction "2Y_4") (pintype "unspecified"))
      (node (ref "R66") (pin "2") (pinfunction "2_2") (pintype "input"))
    )
    (net (code "62") (name "Net-(LED1-A)") (class "Default")
      (node (ref "LED1") (pin "2") (pinfunction "A_2") (pintype "unspecified"))
      (node (ref "R47") (pin "1") (pinfunction "1_1") (pintype "input"))
    )
    (net (code "63") (name "Net-(LED1-K)") (class "Default")
      (node (ref "LED1") (pin "1") (pinfunction "K_1") (pintype "unspecified"))
      (node (ref "U1") (pin "23") (pinfunction "CBUS0_23") (pintype "bidirectional"))
    )
    (net (code "64") (name "Net-(LED2-A)") (class "Default")
      (node (ref "LED2") (pin "2") (pinfunction "A_2") (pintype "unspecified"))
      (node (ref "R48") (pin "1") (pinfunction "1_1") (pintype "input"))
    )
    (net (code "65") (name "Net-(LED2-K)") (class "Default")
      (node (ref "LED2") (pin "1") (pinfunction "K_1") (pintype "unspecified"))
      (node (ref "U1") (pin "22") (pinfunction "CBUS1_22") (pintype "bidirectional"))
    )
    (net (code "66") (name "Net-(P20-Pad1)") (class "Default")
      (node (ref "P20") (pin "1") (pinfunction "1_1") (pintype "input"))
      (node (ref "R75") (pin "2") (pinfunction "2_2") (pintype "input"))
    )
    (net (code "67") (name "Net-(P21-Pad1)") (class "Default")
      (node (ref "P21") (pin "1") (pinfunction "1_1") (pintype "input"))
      (node (ref "R77") (pin "2") (pinfunction "2_2") (pintype "input"))
    )
    (net (code "68") (name "Net-(U1-3V3OUT)") (class "Default")
      (node (ref "C55") (pin "2") (pinfunction "2_2") (pintype "unspecified"))
      (node (ref "U1") (pin "17") (pinfunction "3V3OUT_17") (pintype "output"))
    )
    (net (code "69") (name "Net-(U1-RESET)") (class "Default")
      (node (ref "R49") (pin "2") (pinfunction "2_2") (pintype "unspecified"))
      (node (ref "R50") (pin "1") (pinfunction "1_1") (pintype "unspecified"))
      (node (ref "U1") (pin "19") (pinfunction "RESET_19") (pintype "unspecified"))
    )
    (net (code "70") (name "Net-(U1-RXD)") (class "Default")
      (node (ref "U1") (pin "5") (pinfunction "RXD_5") (pintype "unspecified"))
      (node (ref "U4") (pin "2") (pinfunction "OUTA_2") (pintype "unspecified"))
    )
    (net (code "71") (name "Net-(U1-TXD)") (class "Default")
      (node (ref "U1") (pin "1") (pinfunction "TXD_1") (pintype "output"))
      (node (ref "U4") (pin "3") (pinfunction "INB_3") (pintype "unspecified"))
    )
    (net (code "72") (name "Net-(U1-USBDM)") (class "Default")
      (node (ref "R45") (pin "2") (pinfunction "2_2") (pintype "unspecified"))
      (node (ref "U1") (pin "16") (pinfunction "USBDM_16") (pintype "bidirectional"))
    )
    (net (code "73") (name "Net-(U1-USBDP)") (class "Default")
      (node (ref "R46") (pin "2") (pinfunction "2_2") (pintype "unspecified"))
      (node (ref "U1") (pin "15") (pinfunction "USBDP_15") (pintype "bidirectional"))
    )
    (net (code "74") (name "Net-(U1-VCC)") (class "Default")
      (node (ref "C14") (pin "2") (pinfunction "2_2") (pintype "unspecified"))
      (node (ref "C17") (pin "2") (pinfunction "2_2") (pintype "unspecified"))
      (node (ref "C53") (pin "2") (pinfunction "2_2") (pintype "unspecified"))
      (node (ref "C54") (pin "2") (pinfunction "2_2") (pintype "input"))
      (node (ref "L5") (pin "2") (pinfunction "2_2") (pintype "unspecified"))
      (node (ref "R47") (pin "2") (pinfunction "2_2") (pintype "input"))
      (node (ref "R48") (pin "2") (pinfunction "2_2") (pintype "input"))
      (node (ref "R50") (pin "2") (pinfunction "2_2") (pintype "unspecified"))
      (node (ref "U1") (pin "20") (pinfunction "VCC_20") (pintype "passive"))
      (node (ref "U1") (pin "4") (pinfunction "VCCIO_4") (pintype "passive"))
      (node (ref "U4") (pin "1") (pinfunction "VCC1_1") (pintype "unspecified"))
    )
    (net (code "75") (name "Net-(USB1-D+)") (class "Default")
      (node (ref "R46") (pin "1") (pinfunction "1_1") (pintype "unspecified"))
      (node (ref "USB1") (pin "3") (pinfunction "D+_3") (pintype "input"))
    )
    (net (code "76") (name "Net-(USB1-D-)") (class "Default")
      (node (ref "R45") (pin "1") (pinfunction "1_1") (pintype "unspecified"))
      (node (ref "USB1") (pin "2") (pinfunction "D-_2") (pintype "input"))
    )
    (net (code "77") (name "Net-(USB1-VCC)") (class "Default")
      (node (ref "C16") (pin "1") (pinfunction "1_1") (pintype "input"))
      (node (ref "C56") (pin "2") (pinfunction "2_2") (pintype "unspecified"))
      (node (ref "L5") (pin "1") (pinfunction "1_1") (pintype "unspecified"))
      (node (ref "USB1") (pin "1") (pinfunction "VCC_1") (pintype "input"))
    )
    (net (code "78") (name "Net-(VD10-C)") (class "Default")
      (node (ref "P61") (pin "1") (pinfunction "1_1") (pintype "input"))
      (node (ref "P62") (pin "1") (pinfunction "1_1") (pintype "input"))
      (node (ref "P63") (pin "1") (pinfunction "1_1") (pintype "input"))
      (node (ref "P64") (pin "1") (pinfunction "1_1") (pintype "input"))
      (node (ref "P65") (pin "1") (pinfunction "1_1") (pintype "input"))
      (node (ref "P66") (pin "1") (pinfunction "1_1") (pintype "input"))
      (node (ref "R44") (pin "1") (pinfunction "1_1") (pintype "input"))
      (node (ref "R56") (pin "1") (pinfunction "1_1") (pintype "input"))
      (node (ref "VD10") (pin "2") (pinfunction "C_2") (pintype "unspecified"))
      (node (ref "VD13") (pin "2") (pinfunction "C_2") (pintype "unspecified"))
      (node (ref "VT28") (pin "3") (pinfunction "S_3") (pintype "unspecified"))
      (node (ref "VT29") (pin "3") (pinfunction "S_3") (pintype "unspecified"))
      (node (ref "VT30") (pin "3") (pinfunction "S_3") (pintype "unspecified"))
      (node (ref "VT31") (pin "3") (pinfunction "S_3") (pintype "unspecified"))
    )
    (net (code "79") (name "Net-(VT1-G)") (class "Default")
      (node (ref "R26") (pin "2") (pinfunction "2_2") (pintype "input"))
      (node (ref "R8") (pin "1") (pinfunction "1_1") (pintype "input"))
      (node (ref "VT1") (pin "1") (pinfunction "G_1") (pintype "unspecified"))
      (node (ref "VT2") (pin "1") (pinfunction "G_1") (pintype "unspecified"))
    )
    (net (code "80") (name "Net-(VT3-G)") (class "Default")
      (node (ref "R1") (pin "1") (pinfunction "1_1") (pintype "input"))
      (node (ref "R19") (pin "2") (pinfunction "2_2") (pintype "input"))
      (node (ref "VT3") (pin "1") (pinfunction "G_1") (pintype "unspecified"))
      (node (ref "VT4") (pin "1") (pinfunction "G_1") (pintype "unspecified"))
    )
    (net (code "81") (name "Net-(VT5-G)") (class "Default")
      (node (ref "R20") (pin "2") (pinfunction "2_2") (pintype "input"))
      (node (ref "R51") (pin "2") (pinfunction "2_2") (pintype "input"))
      (node (ref "VT5") (pin "1") (pinfunction "G_1") (pintype "unspecified"))
      (node (ref "VT6") (pin "1") (pinfunction "G_1") (pintype "unspecified"))
    )
    (net (code "82") (name "Net-(VT7-G)") (class "Default")
      (node (ref "R21") (pin "2") (pinfunction "2_2") (pintype "input"))
      (node (ref "R52") (pin "2") (pinfunction "2_2") (pintype "input"))
      (node (ref "VT7") (pin "1") (pinfunction "G_1") (pintype "unspecified"))
      (node (ref "VT8") (pin "1") (pinfunction "G_1") (pintype "unspecified"))
    )
    (net (code "83") (name "Net-(VT10-G)") (class "Default")
      (node (ref "R22") (pin "2") (pinfunction "2_2") (pintype "input"))
      (node (ref "R27") (pin "2") (pinfunction "2_2") (pintype "input"))
      (node (ref "VT10") (pin "1") (pinfunction "G_1") (pintype "unspecified"))
      (node (ref "VT9") (pin "1") (pinfunction "G_1") (pintype "unspecified"))
    )
    (net (code "84") (name "Net-(VT11-G)") (class "Default")
      (node (ref "R23") (pin "1") (pinfunction "1_1") (pintype "input"))
      (node (ref "R36") (pin "1") (pinfunction "1_1") (pintype "input"))
      (node (ref "VT11") (pin "1") (pinfunction "G_1") (pintype "unspecified"))
      (node (ref "VT13") (pin "1") (pinfunction "G_1") (pintype "unspecified"))
    )
    (net (code "85") (name "Net-(VT12-D)") (class "Default")
      (node (ref "B1") (pin "2") (pinfunction "2_2") (pintype "unspecified"))
      (node (ref "VT12") (pin "3") (pinfunction "D_3") (pintype "unspecified"))
    )
    (net (code "86") (name "Net-(VT14-G)") (class "Default")
      (node (ref "R2") (pin "1") (pinfunction "1_1") (pintype "input"))
      (node (ref "R24") (pin "2") (pinfunction "2_2") (pintype "input"))
      (node (ref "VT14") (pin "1") (pinfunction "G_1") (pintype "unspecified"))
      (node (ref "VT15") (pin "1") (pinfunction "G_1") (pintype "unspecified"))
    )
    (net (code "87") (name "Net-(VT16-G)") (class "Default")
      (node (ref "R25") (pin "1") (pinfunction "1_1") (pintype "input"))
      (node (ref "R32") (pin "1") (pinfunction "1_1") (pintype "input"))
      (node (ref "VT16") (pin "1") (pinfunction "G_1") (pintype "unspecified"))
      (node (ref "VT17") (pin "1") (pinfunction "G_1") (pintype "unspecified"))
    )
    (net (code "88") (name "Net-(VT18-G)") (class "Default")
      (node (ref "R64") (pin "1") (pinfunction "1_1") (pintype "input"))
      (node (ref "VT18") (pin "1") (pinfunction "G_1") (pintype "unspecified"))
      (node (ref "VT20") (pin "3") (pinfunction "D_3") (pintype "unspecified"))
    )
    (net (code "89") (name "Net-(VT19-G)") (class "Default")
      (node (ref "R63") (pin "2") (pinfunction "2_2") (pintype "input"))
      (node (ref "VT19") (pin "1") (pinfunction "G_1") (pintype "unspecified"))
      (node (ref "VT21") (pin "3") (pinfunction "D_3") (pintype "unspecified"))
    )
    (net (code "90") (name "Net-(VT22-S)") (class "Default")
      (node (ref "R70") (pin "2") (pinfunction "2_2") (pintype "input"))
      (node (ref "VT22") (pin "3") (pinfunction "S_3") (pintype "unspecified"))
    )
    (net (code "91") (name "Net-(VT23-S)") (class "Default")
      (node (ref "R69") (pin "2") (pinfunction "2_2") (pintype "input"))
      (node (ref "VT23") (pin "3") (pinfunction "S_3") (pintype "unspecified"))
    )
    (net (code "92") (name "Net-(VT24-G)") (class "Default")
      (node (ref "R40") (pin "1") (pinfunction "1_1") (pintype "input"))
      (node (ref "R41") (pin "2") (pinfunction "2_2") (pintype "input"))
      (node (ref "VT24") (pin "1") (pinfunction "G_1") (pintype "unspecified"))
      (node (ref "VT25") (pin "1") (pinfunction "G_1") (pintype "unspecified"))
    )
    (net (code "93") (name "Net-(VT26-G)") (class "Default")
      (node (ref "R42") (pin "1") (pinfunction "1_1") (pintype "input"))
      (node (ref "R43") (pin "2") (pinfunction "2_2") (pintype "input"))
      (node (ref "VT26") (pin "1") (pinfunction "G_1") (pintype "unspecified"))
      (node (ref "VT27") (pin "1") (pinfunction "G_1") (pintype "unspecified"))
    )
    (net (code "94") (name "Net-(VT28-G)") (class "Default")
      (node (ref "R44") (pin "2") (pinfunction "2_2") (pintype "input"))
      (node (ref "R53") (pin "1") (pinfunction "1_1") (pintype "input"))
      (node (ref "VT28") (pin "1") (pinfunction "G_1") (pintype "unspecified"))
      (node (ref "VT29") (pin "1") (pinfunction "G_1") (pintype "unspecified"))
    )
    (net (code "95") (name "Net-(VT30-G)") (class "Default")
      (node (ref "R56") (pin "2") (pinfunction "2_2") (pintype "input"))
      (node (ref "R57") (pin "1") (pinfunction "1_1") (pintype "input"))
      (node (ref "VT30") (pin "1") (pinfunction "G_1") (pintype "unspecified"))
      (node (ref "VT31") (pin "1") (pinfunction "G_1") (pintype "unspecified"))
    )
    (net (code "96") (name "OSC32_IN") (class "Default")
      (node (ref "C39") (pin "1") (pinfunction "1_1") (pintype "input"))
      (node (ref "X2") (pin "1") (pinfunction "OSC1_1") (pintype "input"))
    )
    (net (code "97") (name "OSC32_In") (class "Default")
      (node (ref "DD1") (pin "3") (pinfunction "PC14/OSC32_IN/I/O_3") (pintype "unspecified"))
    )
    (net (code "98") (name "OSC32_OUT") (class "Default")
      (node (ref "C40") (pin "1") (pinfunction "1_1") (pintype "input"))
      (node (ref "X2") (pin "2") (pinfunction "OSC2_2") (pintype "input"))
    )
    (net (code "99") (name "OSC32_Out") (class "Default")
      (node (ref "DD1") (pin "4") (pinfunction "PC15/OSC32_OUT/I/O_4") (pintype "unspecified"))
    )
    (net (code "100") (name "OSC_In") (class "Default")
      (node (ref "C38") (pin "2") (pinfunction "2_2") (pintype "input"))
      (node (ref "DD1") (pin "5") (pinfunction "PF0/OSC_IN/I/O/RCC_OSC_IN/_5") (pintype "unspecified"))
      (node (ref "Q3") (pin "2") (pinfunction "OSC2_2") (pintype "input"))
    )
    (net (code "101") (name "OSC_Out") (class "Default")
      (node (ref "C13") (pin "2") (pinfunction "2_2") (pintype "input"))
      (node (ref "DD1") (pin "6") (pinfunction "PF1/OSC_OUT/I/O_6") (pintype "unspecified"))
      (node (ref "Q3") (pin "1") (pinfunction "OSC1_1") (pintype "input"))
    )
    (net (code "102") (name "PGND") (class "Default")
      (node (ref "C33") (pin "1") (pinfunction "1_1") (pintype "input"))
      (node (ref "C34") (pin "1") (pinfunction "1_1") (pintype "input"))
      (node (ref "C42") (pin "1") (pinfunction "1_1") (pintype "input"))
      (node (ref "C43") (pin "1") (pinfunction "1_1") (pintype "input"))
      (node (ref "C44") (pin "1") (pinfunction "1_1") (pintype "input"))
      (node (ref "C45") (pin "1") (pinfunction "1_1") (pintype "input"))
      (node (ref "C46") (pin "1") (pinfunction "1_1") (pintype "input"))
      (node (ref "C47") (pin "1") (pinfunction "1_1") (pintype "input"))
      (node (ref "C48") (pin "1") (pinfunction "1_1") (pintype "input"))
      (node (ref "C49") (pin "1") (pinfunction "1_1") (pintype "input"))
      (node (ref "L2") (pin "1") (pinfunction "1_1") (pintype "unspecified"))
      (node (ref "P48") (pin "1") (pinfunction "1_1") (pintype "input"))
      (node (ref "P49") (pin "1") (pinfunction "1_1") (pintype "input"))
      (node (ref "P50") (pin "1") (pinfunction "1_1") (pintype "input"))
      (node (ref "P51") (pin "1") (pinfunction "1_1") (pintype "input"))
      (node (ref "P52") (pin "1") (pinfunction "1_1") (pintype "input"))
      (node (ref "P53") (pin "1") (pinfunction "1_1") (pintype "input"))
      (node (ref "P54") (pin "1") (pinfunction "1_1") (pintype "input"))
      (node (ref "P55") (pin "1") (pinfunction "1_1") (pintype "input"))
      (node (ref "P56") (pin "1") (pinfunction "1_1") (pintype "input"))
      (node (ref "P57") (pin "1") (pinfunction "1_1") (pintype "input"))
      (node (ref "P58") (pin "1") (pinfunction "1_1") (pintype "input"))
      (node (ref "P59") (pin "1") (pinfunction "1_1") (pintype "input"))
      (node (ref "R19") (pin "1") (pinfunction "1_1") (pintype "input"))
      (node (ref "R41") (pin "1") (pinfunction "1_1") (pintype "input"))
      (node (ref "R43") (pin "1") (pinfunction "1_1") (pintype "input"))
      (node (ref "R69") (pin "1") (pinfunction "1_1") (pintype "input"))
      (node (ref "R70") (pin "1") (pinfunction "1_1") (pintype "input"))
      (node (ref "R71") (pin "2") (pinfunction "2_2") (pintype "input"))
      (node (ref "R72") (pin "2") (pinfunction "2_2") (pintype "input"))
      (node (ref "R8") (pin "2") (pinfunction "2_2") (pintype "input"))
      (node (ref "VD11") (pin "1") (pinfunction "AC_1") (pintype "unspecified"))
      (node (ref "VD11") (pin "3") (pinfunction "AC_3") (pintype "unspecified"))
      (node (ref "VD12") (pin "1") (pinfunction "AC_1") (pintype "unspecified"))
      (node (ref "VD12") (pin "3") (pinfunction "AC_3") (pintype "unspecified"))
      (node (ref "VT1") (pin "3") (pinfunction "S_3") (pintype "unspecified"))
      (node (ref "VT2") (pin "3") (pinfunction "S_3") (pintype "unspecified"))
      (node (ref "VT24") (pin "3") (pinfunction "S_3") (pintype "unspecified"))
      (node (ref "VT25") (pin "3") (pinfunction "S_3") (pintype "unspecified"))
      (node (ref "VT26") (pin "3") (pinfunction "S_3") (pintype "unspecified"))
      (node (ref "VT27") (pin "3") (pinfunction "S_3") (pintype "unspecified"))
      (node (ref "VT3") (pin "3") (pinfunction "S_3") (pintype "unspecified"))
      (node (ref "VT4") (pin "3") (pinfunction "S_3") (pintype "unspecified"))
    )
    (net (code "103") (name "Right_Dwn") (class "Default")
      (node (ref "D2") (pin "4") (pinfunction "LO_4") (pintype "unspecified"))
      (node (ref "D4") (pin "6") (pinfunction "OUT_6") (pintype "unspecified"))
      (node (ref "D4") (pin "7") (pinfunction "OUT_7") (pintype "unspecified"))
      (node (ref "R1") (pin "2") (pinfunction "2_2") (pintype "input"))
    )
    (net (code "104") (name "Right_Dwn_In") (class "Default")
      (node (ref "D2") (pin "2") (pinfunction "LIN_2") (pintype "unspecified"))
      (node (ref "D4") (pin "2") (pinfunction "IN_2") (pintype "unspecified"))
      (node (ref "R31") (pin "2") (pinfunction "2_2") (pintype "input"))
    )
    (net (code "105") (name "Right_Rec") (class "Default")
      (node (ref "D17") (pin "3") (pinfunction "IN+_3") (pintype "unspecified"))
      (node (ref "D19") (pin "1") (pinfunction "1A_1") (pintype "unspecified"))
      (node (ref "R10") (pin "2") (pinfunction "2_2") (pintype "input"))
      (node (ref "R65") (pin "2") (pinfunction "2_2") (pintype "input"))
    )
    (net (code "106") (name "Right_Up1") (class "Default")
      (node (ref "D2") (pin "7") (pinfunction "HO_7") (pintype "unspecified"))
      (node (ref "D6") (pin "7") (pinfunction "TG_7") (pintype "output"))
      (node (ref "R36") (pin "2") (pinfunction "2_2") (pintype "input"))
    )
    (net (code "107") (name "Right_Up1_In") (class "Default")
      (node (ref "D2") (pin "1") (pinfunction "HIN_1") (pintype "unspecified"))
      (node (ref "D6") (pin "1") (pinfunction "INP_1") (pintype "unspecified"))
      (node (ref "R4") (pin "2") (pinfunction "2_2") (pintype "input"))
    )
    (net (code "108") (name "Right_Up2") (class "Default")
      (node (ref "D7") (pin "7") (pinfunction "TG_7") (pintype "output"))
      (node (ref "D9") (pin "7") (pinfunction "HO_7") (pintype "unspecified"))
      (node (ref "R32") (pin "2") (pinfunction "2_2") (pintype "input"))
    )
    (net (code "109") (name "Right_Up2_In") (class "Default")
      (node (ref "D7") (pin "1") (pinfunction "INP_1") (pintype "unspecified"))
      (node (ref "D9") (pin "1") (pinfunction "HIN_1") (pintype "unspecified"))
      (node (ref "R13") (pin "1") (pinfunction "1_1") (pintype "input"))
    )
    (net (code "110") (name "Right_Up3") (class "Default")
      (node (ref "D13") (pin "7") (pinfunction "HO_7") (pintype "unspecified"))
      (node (ref "D14") (pin "7") (pinfunction "TG_7") (pintype "output"))
      (node (ref "R2") (pin "2") (pinfunction "2_2") (pintype "input"))
    )
    (net (code "111") (name "Right_Up3_In") (class "Default")
      (node (ref "D13") (pin "1") (pinfunction "HIN_1") (pintype "unspecified"))
      (node (ref "D14") (pin "1") (pinfunction "INP_1") (pintype "unspecified"))
      (node (ref "R15") (pin "1") (pinfunction "1_1") (pintype "input"))
    )
    (net (code "112") (name "SWDCLK") (class "Default")
      (node (ref "DD1") (pin "49") (pinfunction "PA14/I/O_49") (pintype "unspecified"))
      (node (ref "H3") (pin "3") (pinfunction "3_3") (pintype "input"))
    )
    (net (code "113") (name "SWDIO") (class "Default")
      (node (ref "DD1") (pin "46") (pinfunction "PA13/I/O_46") (pintype "unspecified"))
      (node (ref "H3") (pin "1") (pinfunction "1_1") (pintype "input"))
    )
    (net (code "114") (name "Tim2_Ch1") (class "Default")
      (node (ref "DD1") (pin "14") (pinfunction "PA0/I/O/TIM2_CH1_14") (pintype "unspecified"))
      (node (ref "R7") (pin "2") (pinfunction "2_2") (pintype "input"))
    )
    (net (code "115") (name "Tim2_Ch2") (class "Default")
      (node (ref "DD1") (pin "15") (pinfunction "PA1/I/O/TIM2_CH2_15") (pintype "unspecified"))
      (node (ref "R30") (pin "2") (pinfunction "2_2") (pintype "input"))
    )
    (net (code "116") (name "Tim15_Ch1") (class "Default")
      (node (ref "DD1") (pin "16") (pinfunction "PA2/I/O/ADC1_IN3_16") (pintype "unspecified"))
      (node (ref "R59") (pin "2") (pinfunction "2_2") (pintype "input"))
    )
    (net (code "117") (name "Tim15_Ch2") (class "Default")
      (node (ref "DD1") (pin "17") (pinfunction "PA3/I/O_17") (pintype "unspecified"))
      (node (ref "R62") (pin "2") (pinfunction "2_2") (pintype "input"))
    )
    (net (code "118") (name "UGND") (class "Default")
      (node (ref "C14") (pin "1") (pinfunction "1_1") (pintype "unspecified"))
      (node (ref "C16") (pin "2") (pinfunction "2_2") (pintype "input"))
      (node (ref "C17") (pin "1") (pinfunction "1_1") (pintype "unspecified"))
      (node (ref "C53") (pin "1") (pinfunction "1_1") (pintype "unspecified"))
      (node (ref "C54") (pin "1") (pinfunction "1_1") (pintype "input"))
      (node (ref "C55") (pin "1") (pinfunction "1_1") (pintype "unspecified"))
      (node (ref "C56") (pin "1") (pinfunction "1_1") (pintype "unspecified"))
      (node (ref "R49") (pin "1") (pinfunction "1_1") (pintype "unspecified"))
      (node (ref "U1") (pin "18") (pinfunction "GND_18") (pintype "passive"))
      (node (ref "U1") (pin "21") (pinfunction "GND_21") (pintype "passive"))
      (node (ref "U1") (pin "25") (pinfunction "AGND_25") (pintype "passive"))
      (node (ref "U1") (pin "26") (pinfunction "TEST_26") (pintype "unspecified"))
      (node (ref "U1") (pin "7") (pinfunction "GND_7") (pintype "passive"))
      (node (ref "U4") (pin "4") (pinfunction "GND1_4") (pintype "unspecified"))
      (node (ref "USB1") (pin "4") (pinfunction "GND_4") (pintype "input"))
      (node (ref "USB1") (pin "5") (pinfunction "EH_5") (pintype "unspecified"))
    )
    (net (code "119") (name "USART1_RX") (class "Default")
      (node (ref "U4") (pin "6") (pinfunction "OUTB_6") (pintype "unspecified"))
    )
    (net (code "120") (name "USART1_TX") (class "Default")
      (node (ref "U4") (pin "7") (pinfunction "INA_7") (pintype "unspecified"))
    )
    (net (code "121") (name "Usart1_RX") (class "Default")
      (node (ref "DD1") (pin "59") (pinfunction "PB7/I/O_59") (pintype "unspecified"))
    )
    (net (code "122") (name "Usart1_TX") (class "Default")
      (node (ref "DD1") (pin "58") (pinfunction "PB6/I/O_58") (pintype "unspecified"))
    )
    (net (code "123") (name "VBAT") (class "Default")
      (node (ref "DD1") (pin "1") (pinfunction "VBAT/Power_1") (pintype "unspecified"))
      (node (ref "H1") (pin "3") (pinfunction "3_3") (pintype "input"))
    )
    (net (code "124") (name "VCC") (class "Default")
      (node (ref "C1") (pin "2") (pinfunction "2_2") (pintype "input"))
      (node (ref "C10") (pin "2") (pinfunction "2_2") (pintype "input"))
      (node (ref "C11") (pin "2") (pinfunction "2_2") (pintype "input"))
      (node (ref "C2") (pin "2") (pinfunction "2_2") (pintype "input"))
      (node (ref "C20") (pin "2") (pinfunction "2_2") (pintype "input"))
      (node (ref "C21") (pin "2") (pinfunction "2_2") (pintype "input"))
      (node (ref "C22") (pin "2") (pinfunction "2_2") (pintype "input"))
      (node (ref "C23") (pin "2") (pinfunction "2_2") (pintype "input"))
      (node (ref "C27") (pin "2") (pinfunction "2_2") (pintype "input"))
      (node (ref "C35") (pin "2") (pinfunction "2_2") (pintype "unspecified"))
      (node (ref "C5") (pin "2") (pinfunction "2_2") (pintype "input"))
      (node (ref "C57") (pin "2") (pinfunction "2_2") (pintype "input"))
      (node (ref "C6") (pin "2") (pinfunction "2_2") (pintype "input"))
      (node (ref "C63") (pin "2") (pinfunction "2_2") (pintype "input"))
      (node (ref "C64") (pin "2") (pinfunction "2_2") (pintype "input"))
      (node (ref "C65") (pin "2") (pinfunction "2_2") (pintype "input"))
      (node (ref "C66") (pin "1") (pinfunction "1_1") (pintype "input"))
      (node (ref "C67") (pin "1") (pinfunction "1_1") (pintype "input"))
      (node (ref "D1") (pin "5") (pinfunction "VDD_5") (pintype "unspecified"))
      (node (ref "D10") (pin "5") (pinfunction "VDD_5") (pintype "unspecified"))
      (node (ref "D11") (pin "3") (pinfunction "VCC_3") (pintype "passive"))
      (node (ref "D12") (pin "5") (pinfunction "VDD_5") (pintype "unspecified"))
      (node (ref "D13") (pin "5") (pinfunction "VDD_5") (pintype "unspecified"))
      (node (ref "D14") (pin "3") (pinfunction "VCC_3") (pintype "passive"))
      (node (ref "D2") (pin "5") (pinfunction "VDD_5") (pintype "unspecified"))
      (node (ref "D3") (pin "1") (pinfunction "VS_1") (pintype "unspecified"))
      (node (ref "D3") (pin "8") (pinfunction "VS_8") (pintype "unspecified"))
      (node (ref "D4") (pin "1") (pinfunction "VS_1") (pintype "unspecified"))
      (node (ref "D4") (pin "8") (pinfunction "VS_8") (pintype "unspecified"))
      (node (ref "D5") (pin "3") (pinfunction "VCC_3") (pintype "passive"))
      (node (ref "D6") (pin "3") (pinfunction "VCC_3") (pintype "passive"))
      (node (ref "D7") (pin "3") (pinfunction "VCC_3") (pintype "passive"))
      (node (ref "D8") (pin "3") (pinfunction "VCC_3") (pintype "passive"))
      (node (ref "D9") (pin "5") (pinfunction "VDD_5") (pintype "unspecified"))
      (node (ref "DA5") (pin "3") (pinfunction "IN_3") (pintype "unspecified"))
      (node (ref "P1") (pin "1") (pinfunction "1_1") (pintype "unspecified"))
      (node (ref "R18") (pin "2") (pinfunction "2_2") (pintype "input"))
      (node (ref "VD1") (pin "1") (pinfunction "A_1") (pintype "unspecified"))
      (node (ref "VD2") (pin "1") (pinfunction "A_1") (pintype "unspecified"))
      (node (ref "VD3") (pin "1") (pinfunction "A_1") (pintype "unspecified"))
      (node (ref "VD4") (pin "1") (pinfunction "A_1") (pintype "unspecified"))
      (node (ref "VD5") (pin "1") (pinfunction "A_1") (pintype "unspecified"))
      (node (ref "VD6") (pin "1") (pinfunction "A_1") (pintype "unspecified"))
      (node (ref "VD7") (pin "2") (pinfunction "K_2") (pintype "unspecified"))
      (node (ref "VD8") (pin "2") (pinfunction "K_2") (pintype "unspecified"))
      (node (ref "VD9") (pin "2") (pinfunction "K_2") (pintype "unspecified"))
    )
    (net (code "125") (name "VOUT") (class "Default")
      (node (ref "C33") (pin "2") (pinfunction "2_2") (pintype "input"))
      (node (ref "C34") (pin "2") (pinfunction "2_2") (pintype "input"))
      (node (ref "C42") (pin "2") (pinfunction "2_2") (pintype "input"))
      (node (ref "C43") (pin "2") (pinfunction "2_2") (pintype "input"))
      (node (ref "C44") (pin "2") (pinfunction "2_2") (pintype "input"))
      (node (ref "C45") (pin "2") (pinfunction "2_2") (pintype "input"))
      (node (ref "C46") (pin "2") (pinfunction "2_2") (pintype "input"))
      (node (ref "C47") (pin "2") (pinfunction "2_2") (pintype "input"))
      (node (ref "C48") (pin "2") (pinfunction "2_2") (pintype "input"))
      (node (ref "C49") (pin "2") (pinfunction "2_2") (pintype "input"))
      (node (ref "C50") (pin "1") (pinfunction "1_1") (pintype "input"))
      (node (ref "C51") (pin "1") (pinfunction "1_1") (pintype "input"))
      (node (ref "C52") (pin "1") (pinfunction "1_1") (pintype "input"))
      (node (ref "C58") (pin "1") (pinfunction "1_1") (pintype "input"))
      (node (ref "D15") (pin "1") (pinfunction "EN_1") (pintype "unspecified"))
      (node (ref "D15") (pin "5") (pinfunction "VDD_5") (pintype "unspecified"))
      (node (ref "D16") (pin "1") (pinfunction "EN_1") (pintype "unspecified"))
      (node (ref "D16") (pin "5") (pinfunction "VDD_5") (pintype "unspecified"))
      (node (ref "D17") (pin "1") (pinfunction "EN_1") (pintype "unspecified"))
      (node (ref "D17") (pin "5") (pinfunction "VDD_5") (pintype "unspecified"))
      (node (ref "D18") (pin "1") (pinfunction "EN_1") (pintype "unspecified"))
      (node (ref "D18") (pin "5") (pinfunction "VDD_5") (pintype "unspecified"))
      (node (ref "P67") (pin "1") (pinfunction "1_1") (pintype "input"))
      (node (ref "P68") (pin "1") (pinfunction "1_1") (pintype "input"))
      (node (ref "P69") (pin "1") (pinfunction "1_1") (pintype "input"))
      (node (ref "P70") (pin "1") (pinfunction "1_1") (pintype "input"))
      (node (ref "P71") (pin "1") (pinfunction "1_1") (pintype "input"))
      (node (ref "P72") (pin "1") (pinfunction "1_1") (pintype "input"))
      (node (ref "P73") (pin "1") (pinfunction "1_1") (pintype "input"))
      (node (ref "P74") (pin "1") (pinfunction "1_1") (pintype "input"))
      (node (ref "P75") (pin "1") (pinfunction "1_1") (pintype "input"))
      (node (ref "P76") (pin "1") (pinfunction "1_1") (pintype "input"))
      (node (ref "P77") (pin "1") (pinfunction "1_1") (pintype "input"))
      (node (ref "P78") (pin "1") (pinfunction "1_1") (pintype "input"))
      (node (ref "R28") (pin "2") (pinfunction "2_2") (pintype "input"))
    )
    (net (code "126") (name "unconnected-(D3-NC-Pad3)") (class "Default")
      (node (ref "D3") (pin "3") (pinfunction "NC_3") (pintype "unspecified"))
    )
    (net (code "127") (name "unconnected-(D4-NC-Pad3)") (class "Default")
      (node (ref "D4") (pin "3") (pinfunction "NC_3") (pintype "unspecified"))
    )
    (net (code "128") (name "unconnected-(D5-NC-Pad5)") (class "Default")
      (node (ref "D5") (pin "5") (pinfunction "NC_5") (pintype "unspecified"))
    )
    (net (code "129") (name "unconnected-(D6-NC-Pad5)") (class "Default")
      (node (ref "D6") (pin "5") (pinfunction "NC_5") (pintype "unspecified"))
    )
    (net (code "130") (name "unconnected-(D7-NC-Pad5)") (class "Default")
      (node (ref "D7") (pin "5") (pinfunction "NC_5") (pintype "unspecified"))
    )
    (net (code "131") (name "unconnected-(D8-NC-Pad5)") (class "Default")
      (node (ref "D8") (pin "5") (pinfunction "NC_5") (pintype "unspecified"))
    )
    (net (code "132") (name "unconnected-(D9-LO-Pad4)") (class "Default")
      (node (ref "D9") (pin "4") (pinfunction "LO_4") (pintype "unspecified"))
    )
    (net (code "133") (name "unconnected-(D10-LO-Pad4)") (class "Default")
      (node (ref "D10") (pin "4") (pinfunction "LO_4") (pintype "unspecified"))
    )
    (net (code "134") (name "unconnected-(D11-NC-Pad5)") (class "Default")
      (node (ref "D11") (pin "5") (pinfunction "NC_5") (pintype "unspecified"))
    )
    (net (code "135") (name "unconnected-(D12-LO-Pad4)") (class "Default")
      (node (ref "D12") (pin "4") (pinfunction "LO_4") (pintype "unspecified"))
    )
    (net (code "136") (name "unconnected-(D13-LO-Pad4)") (class "Default")
      (node (ref "D13") (pin "4") (pinfunction "LO_4") (pintype "unspecified"))
    )
    (net (code "137") (name "unconnected-(D14-NC-Pad5)") (class "Default")
      (node (ref "D14") (pin "5") (pinfunction "NC_5") (pintype "unspecified"))
    )
    (net (code "138") (name "unconnected-(DD1-PA4{slash}I{slash}O{slash}DAC1_OUT1{slash}-Pad20)") (class "Default")
      (node (ref "DD1") (pin "20") (pinfunction "PA4/I/O/DAC1_OUT1/_20") (pintype "unspecified"))
    )
    (net (code "139") (name "unconnected-(DD1-PA5{slash}I{slash}O-Pad21)") (class "Default")
      (node (ref "DD1") (pin "21") (pinfunction "PA5/I/O_21") (pintype "unspecified"))
    )
    (net (code "140") (name "unconnected-(DD1-PA6{slash}I{slash}O{slash}ADC2_IN3OPAMP2_VOUT-Pad22)") (class "Default")
      (node (ref "DD1") (pin "22") (pinfunction "PA6/I/O/ADC2_IN3OPAMP2_VOUT_22") (pintype "unspecified"))
    )
    (net (code "141") (name "unconnected-(DD1-PA7{slash}I{slash}O{slash}COMP2_INP{slash}-Pad23)") (class "Default")
      (node (ref "DD1") (pin "23") (pinfunction "PA7/I/O/COMP2_INP/_23") (pintype "unspecified"))
    )
    (net (code "142") (name "unconnected-(DD1-PA12{slash}Output{slash}GPIO_Output-Pad45)") (class "Default")
      (node (ref "DD1") (pin "45") (pinfunction "PA12/Output/GPIO_Output_45") (pintype "unspecified"))
    )
    (net (code "143") (name "unconnected-(DD1-PA15{slash}I{slash}O-Pad50)") (class "Default")
      (node (ref "DD1") (pin "50") (pinfunction "PA15/I/O_50") (pintype "unspecified"))
    )
    (net (code "144") (name "unconnected-(DD1-PB3{slash}I{slash}O-Pad55)") (class "Default")
      (node (ref "DD1") (pin "55") (pinfunction "PB3/I/O_55") (pintype "unspecified"))
    )
    (net (code "145") (name "unconnected-(DD1-PB4{slash}I{slash}O-Pad56)") (class "Default")
      (node (ref "DD1") (pin "56") (pinfunction "PB4/I/O_56") (pintype "unspecified"))
    )
    (net (code "146") (name "unconnected-(DD1-PB5{slash}I{slash}O-Pad57)") (class "Default")
      (node (ref "DD1") (pin "57") (pinfunction "PB5/I/O_57") (pintype "unspecified"))
    )
    (net (code "147") (name "unconnected-(DD1-PB8{slash}I{slash}O-Pad61)") (class "Default")
      (node (ref "DD1") (pin "61") (pinfunction "PB8/I/O_61") (pintype "unspecified"))
    )
    (net (code "148") (name "unconnected-(DD1-PB9{slash}I{slash}O-Pad62)") (class "Default")
      (node (ref "DD1") (pin "62") (pinfunction "PB9/I/O_62") (pintype "unspecified"))
    )
    (net (code "149") (name "unconnected-(DD1-PB10{slash}I{slash}O-Pad29)") (class "Default")
      (node (ref "DD1") (pin "29") (pinfunction "PB10/I/O_29") (pintype "unspecified"))
    )
    (net (code "150") (name "unconnected-(DD1-PB11{slash}I{slash}O{slash}COMP6_INP{slash}-Pad30)") (class "Default")
      (node (ref "DD1") (pin "30") (pinfunction "PB11/I/O/COMP6_INP/_30") (pintype "unspecified"))
    )
    (net (code "151") (name "unconnected-(DD1-PC4{slash}I{slash}O-Pad24)") (class "Default")
      (node (ref "DD1") (pin "24") (pinfunction "PC4/I/O_24") (pintype "unspecified"))
    )
    (net (code "152") (name "unconnected-(DD1-PC5{slash}I{slash}O-Pad25)") (class "Default")
      (node (ref "DD1") (pin "25") (pinfunction "PC5/I/O_25") (pintype "unspecified"))
    )
    (net (code "153") (name "unconnected-(DD1-PC6{slash}Output{slash}GPIO_Output-Pad37)") (class "Default")
      (node (ref "DD1") (pin "37") (pinfunction "PC6/Output/GPIO_Output_37") (pintype "unspecified"))
    )
    (net (code "154") (name "unconnected-(DD1-PC7{slash}Output{slash}GPIO_Output-Pad38)") (class "Default")
      (node (ref "DD1") (pin "38") (pinfunction "PC7/Output/GPIO_Output_38") (pintype "unspecified"))
    )
    (net (code "155") (name "unconnected-(DD1-PC10{slash}Output{slash}GPIO_Output-Pad51)") (class "Default")
      (node (ref "DD1") (pin "51") (pinfunction "PC10/Output/GPIO_Output_51") (pintype "unspecified"))
    )
    (net (code "156") (name "unconnected-(DD1-PC11{slash}Output{slash}GPIO_Output-Pad52)") (class "Default")
      (node (ref "DD1") (pin "52") (pinfunction "PC11/Output/GPIO_Output_52") (pintype "unspecified"))
    )
    (net (code "157") (name "unconnected-(DD1-PC12{slash}Output{slash}GPIO_Output-Pad53)") (class "Default")
      (node (ref "DD1") (pin "53") (pinfunction "PC12/Output/GPIO_Output_53") (pintype "unspecified"))
    )
    (net (code "158") (name "unconnected-(DD1-PD2{slash}Output{slash}GPIO_Output-Pad54)") (class "Default")
      (node (ref "DD1") (pin "54") (pinfunction "PD2/Output/GPIO_Output_54") (pintype "unspecified"))
    )
    (net (code "159") (name "unconnected-(U1-CBUS2-Pad13)") (class "Default")
      (node (ref "U1") (pin "13") (pinfunction "CBUS2_13") (pintype "bidirectional"))
    )
    (net (code "160") (name "unconnected-(U1-CBUS3-Pad14)") (class "Default")
      (node (ref "U1") (pin "14") (pinfunction "CBUS3_14") (pintype "bidirectional"))
    )
    (net (code "161") (name "unconnected-(U1-CBUS4-Pad12)") (class "Default")
      (node (ref "U1") (pin "12") (pinfunction "CBUS4_12") (pintype "bidirectional"))
    )
    (net (code "162") (name "unconnected-(U1-CTS-Pad11)") (class "Default")
      (node (ref "U1") (pin "11") (pinfunction "CTS_11") (pintype "unspecified"))
    )
    (net (code "163") (name "unconnected-(U1-DCD-Pad10)") (class "Default")
      (node (ref "U1") (pin "10") (pinfunction "DCD_10") (pintype "unspecified"))
    )
    (net (code "164") (name "unconnected-(U1-DSR-Pad9)") (class "Default")
      (node (ref "U1") (pin "9") (pinfunction "DSR_9") (pintype "unspecified"))
    )
    (net (code "165") (name "unconnected-(U1-DTR-Pad2)") (class "Default")
      (node (ref "U1") (pin "2") (pinfunction "DTR_2") (pintype "output"))
    )
    (net (code "166") (name "unconnected-(U1-NC-Pad8)") (class "Default")
      (node (ref "U1") (pin "8") (pinfunction "NC_8") (pintype "unspecified"))
    )
    (net (code "167") (name "unconnected-(U1-NC-Pad24)") (class "Default")
      (node (ref "U1") (pin "24") (pinfunction "NC_24") (pintype "unspecified"))
    )
    (net (code "168") (name "unconnected-(U1-OSCI-Pad27)") (class "Default")
      (node (ref "U1") (pin "27") (pinfunction "OSCI_27") (pintype "unspecified"))
    )
    (net (code "169") (name "unconnected-(U1-OSCO-Pad28)") (class "Default")
      (node (ref "U1") (pin "28") (pinfunction "OSCO_28") (pintype "output"))
    )
    (net (code "170") (name "unconnected-(U1-RI-Pad6)") (class "Default")
      (node (ref "U1") (pin "6") (pinfunction "RI_6") (pintype "unspecified"))
    )
    (net (code "171") (name "unconnected-(U1-RTS-Pad3)") (class "Default")
      (node (ref "U1") (pin "3") (pinfunction "RTS_3") (pintype "output"))
    )
  )
)
